# EDCPSUMK2_2040.net
KiCad netlist of a schematic drawn in EAGLE
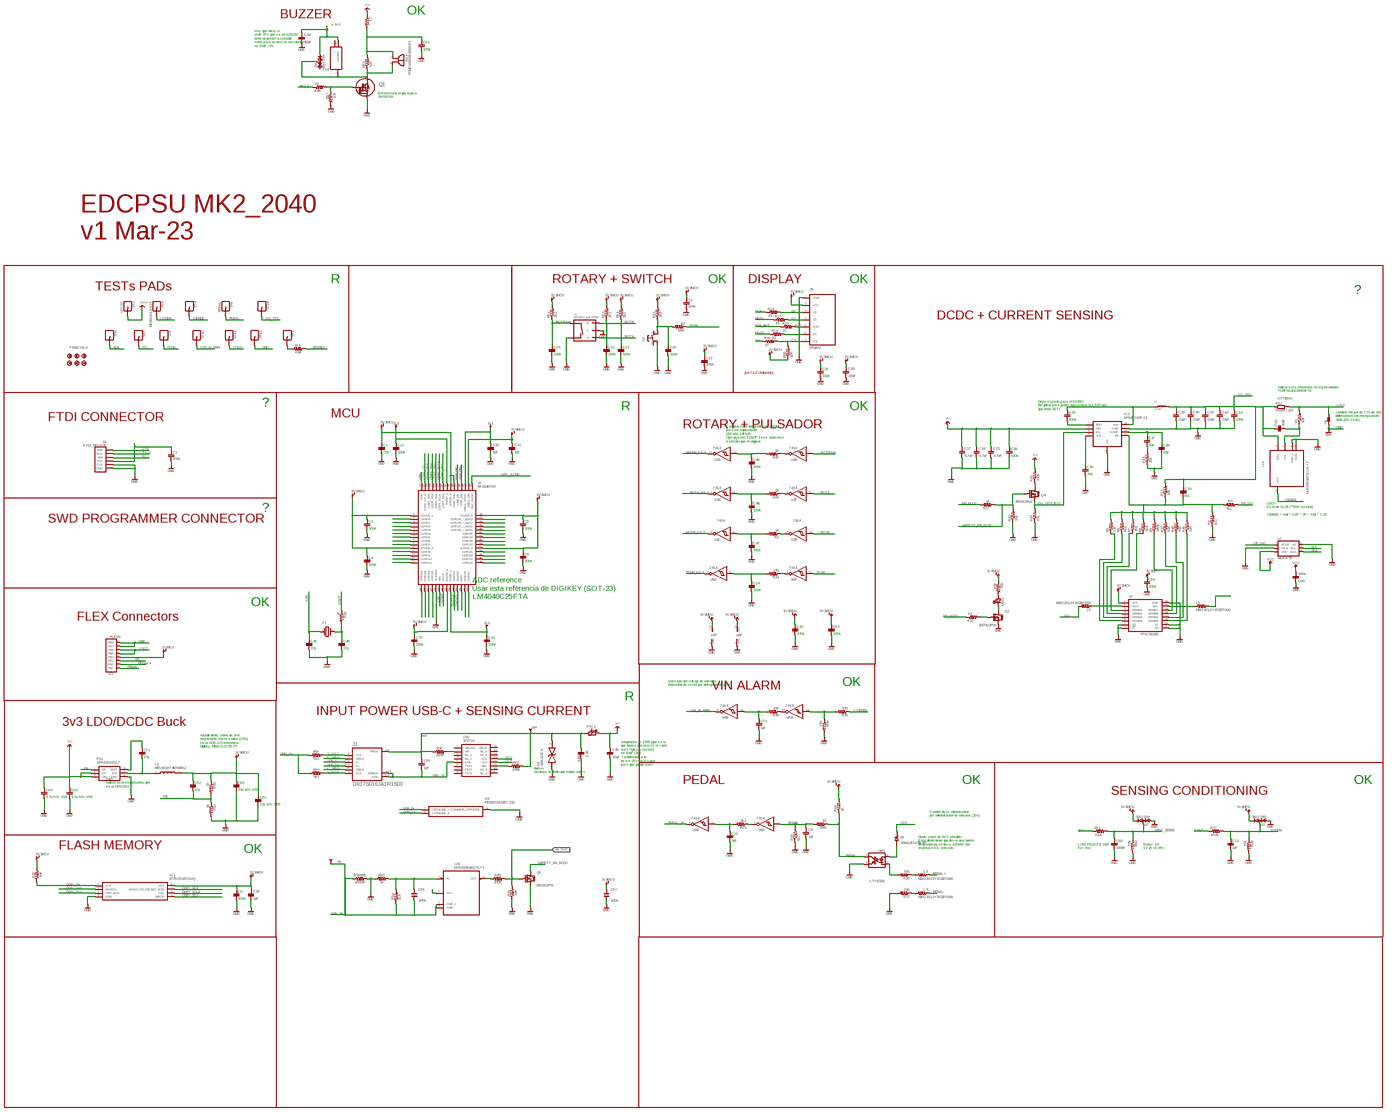
[diagram p0: schematic, sheet 1, overview]
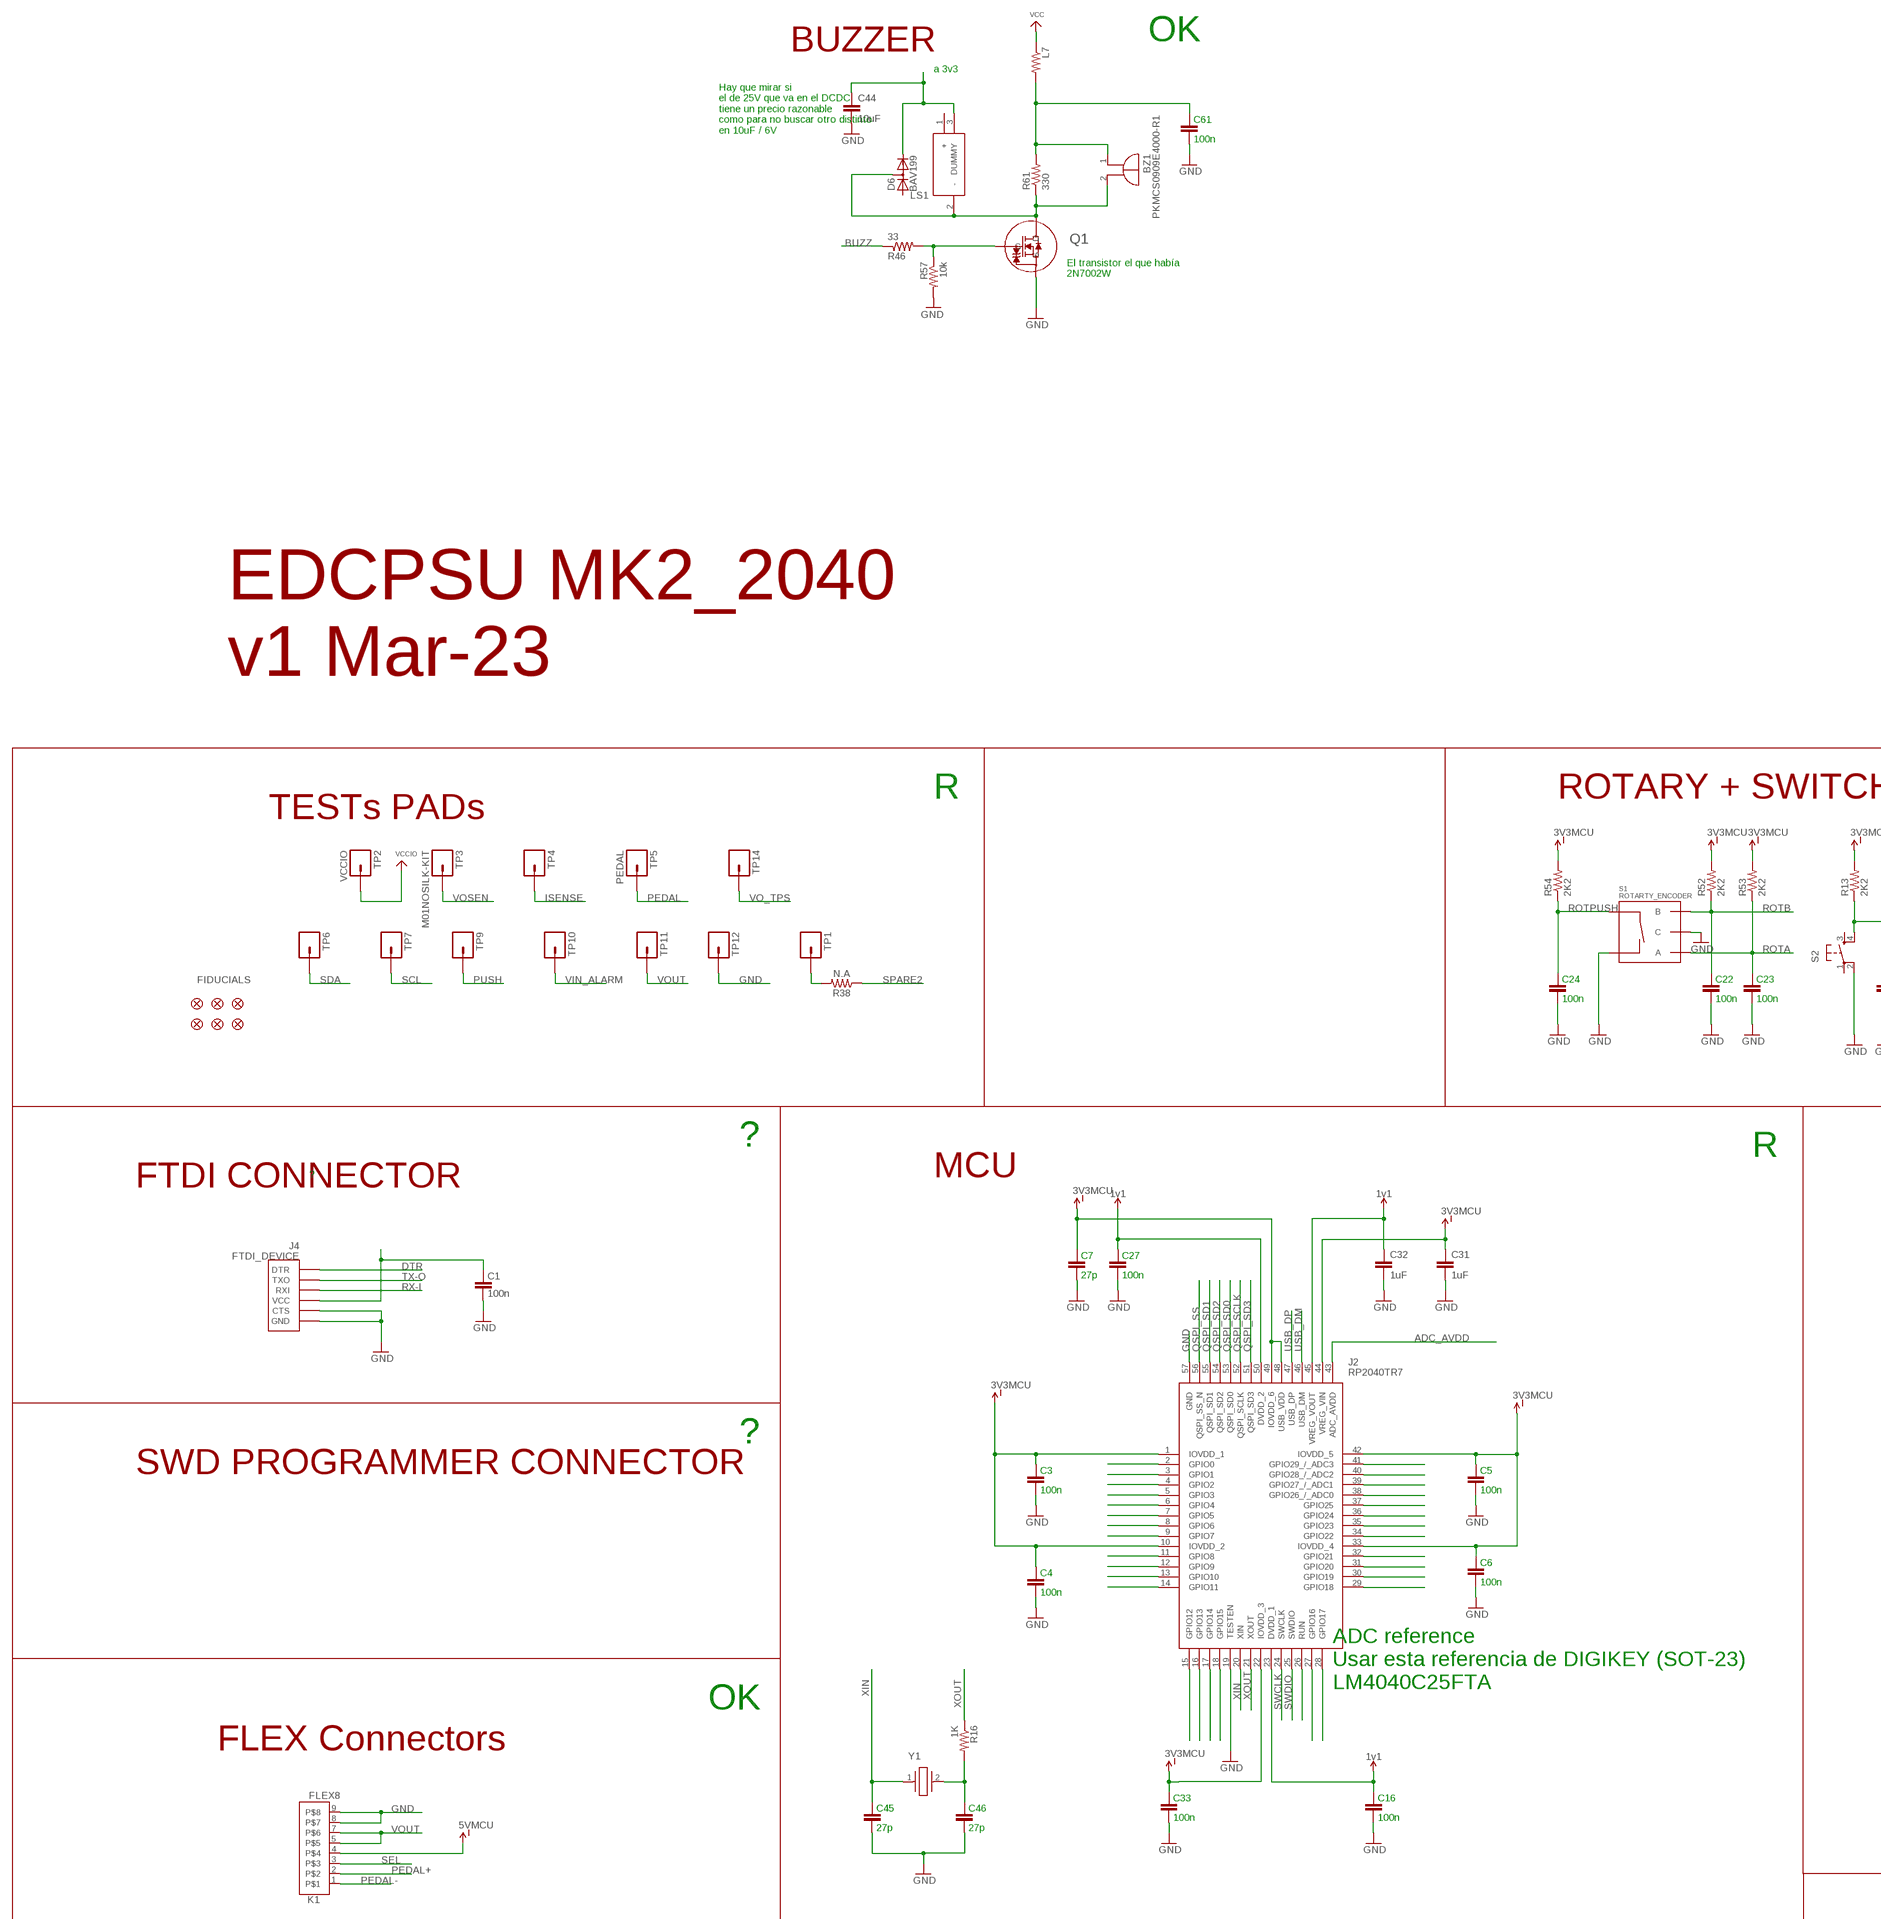
[diagram p1: schematic, sheet 1, part 1 of 4]
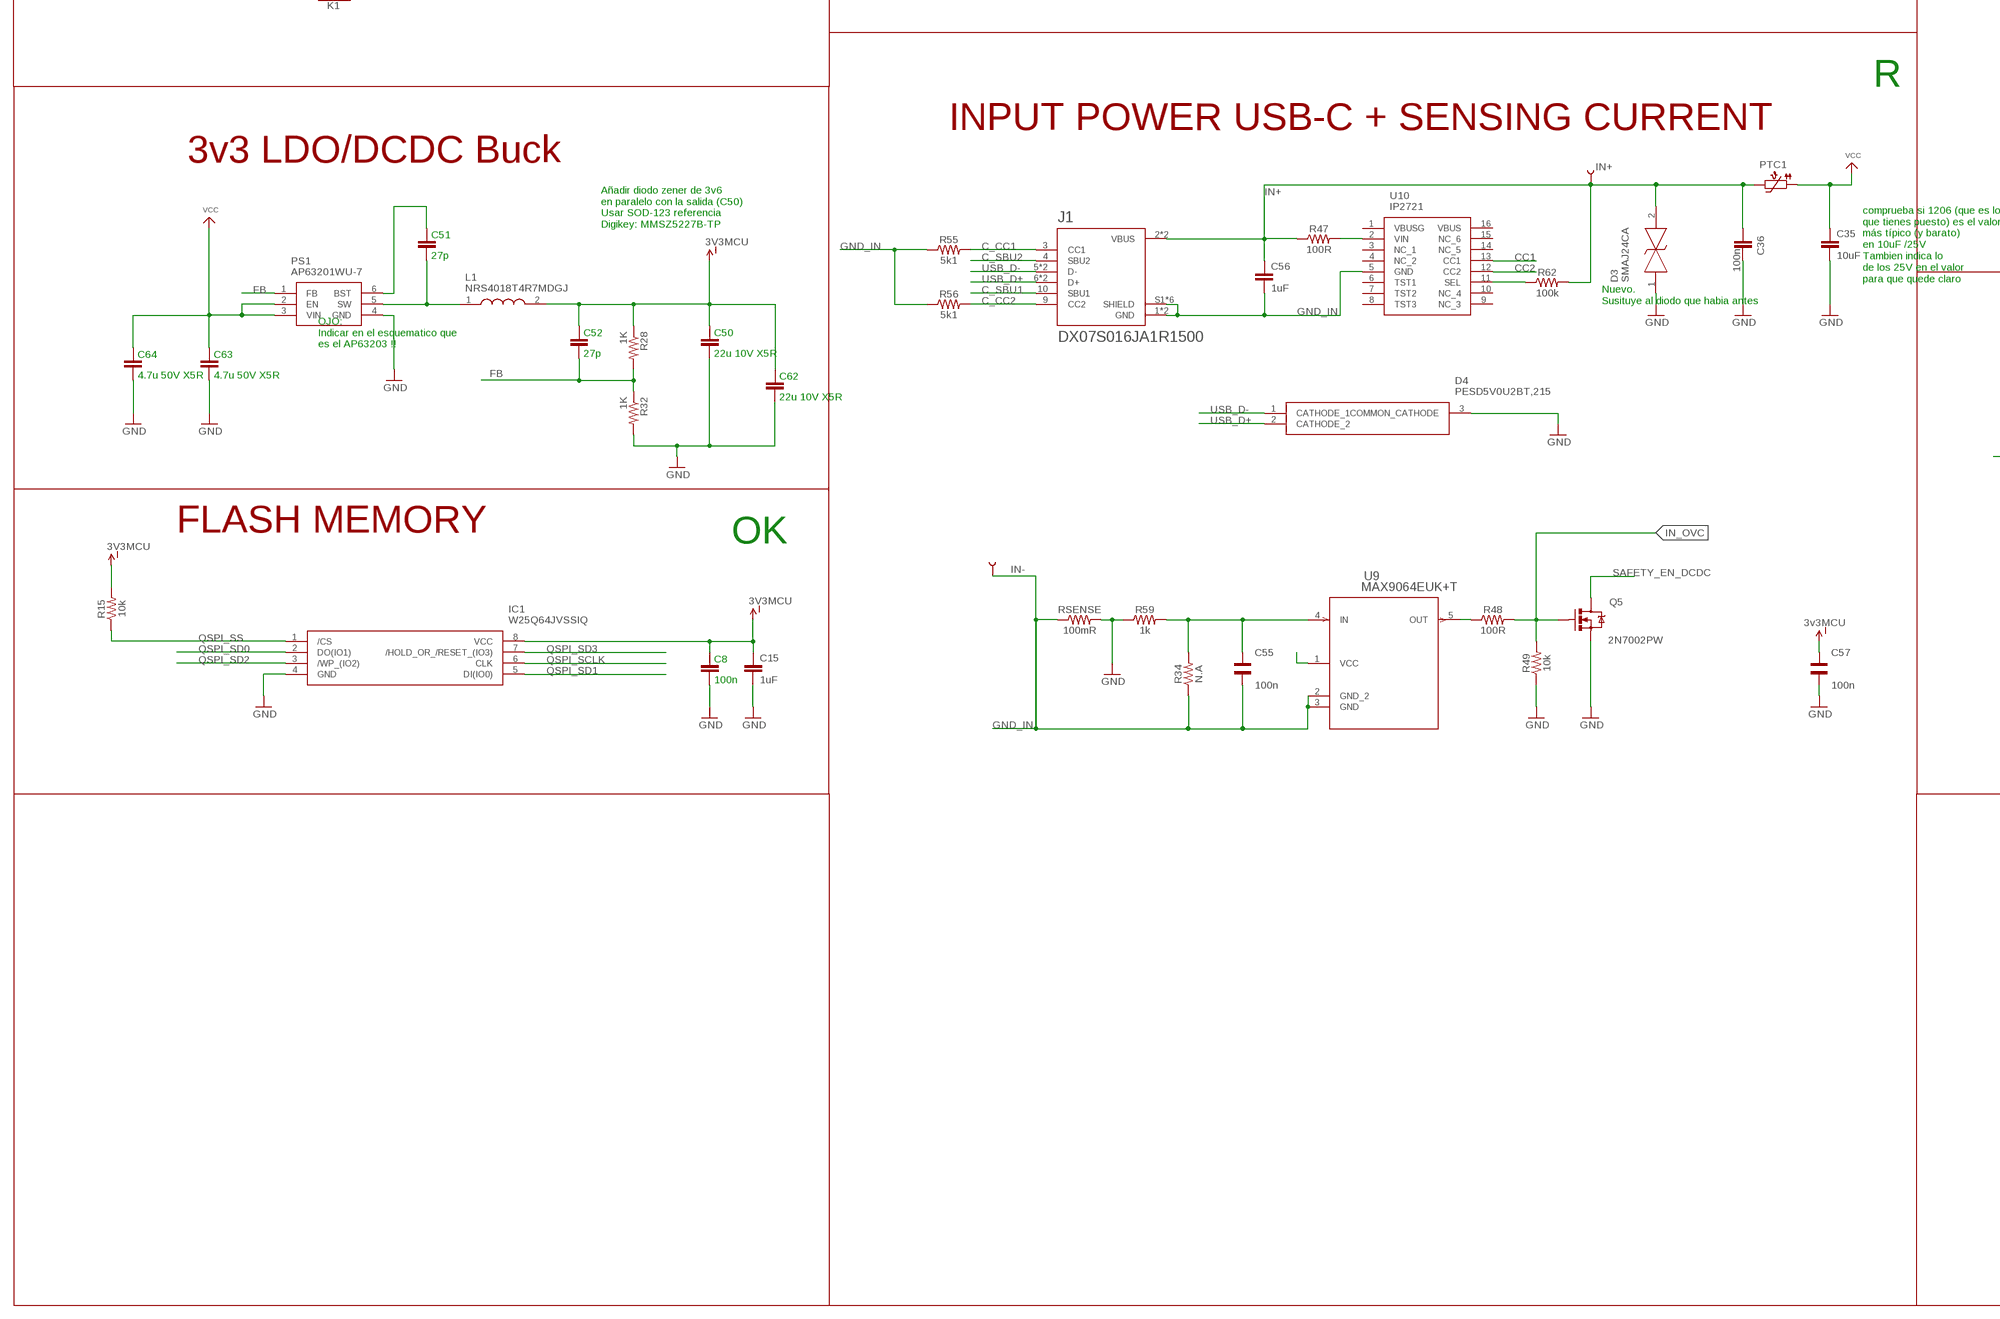
[diagram p2: schematic, sheet 1, part 2 of 4]
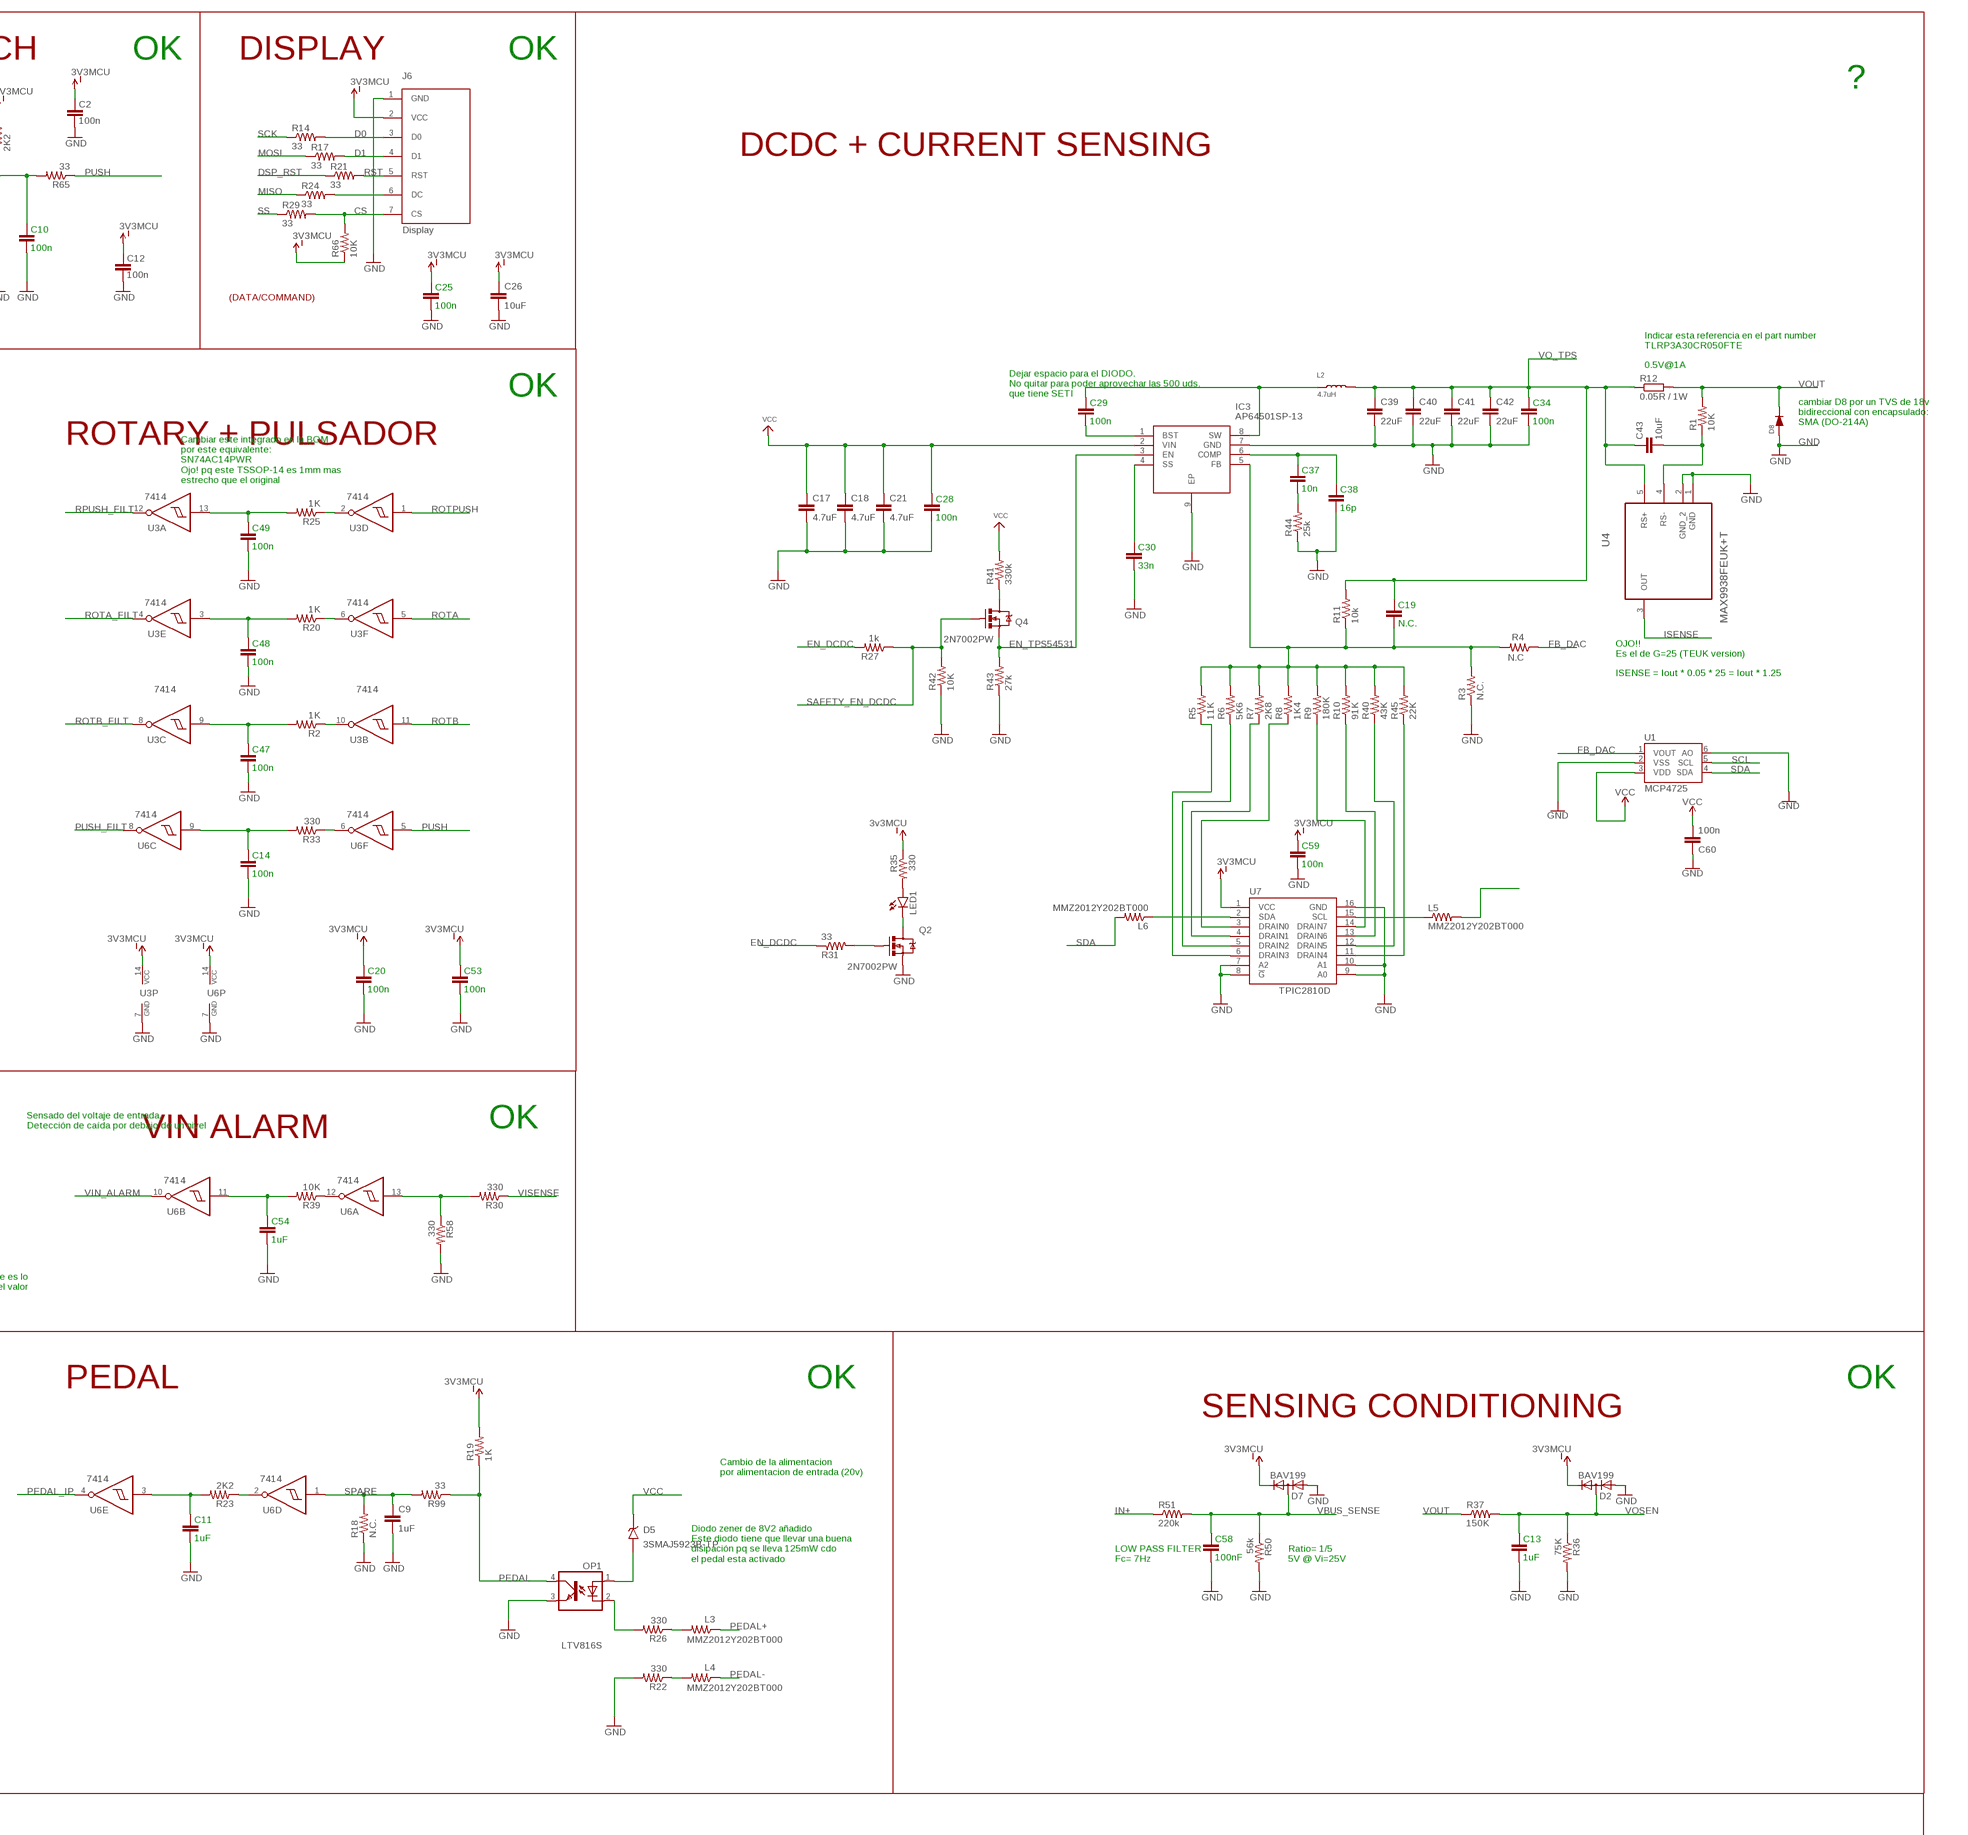
[diagram p3: schematic, sheet 1, part 3 of 4]
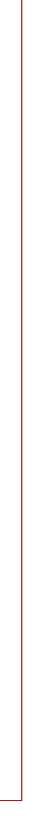
[diagram p4: schematic, sheet 1, part 4 of 4]

(export (version "E")
  (design (tool "Eeschema 10.0.6"))
  (components
    (comp (ref "BZ1")
      (value "PKMCS0909E4000-R1")
      (footprint "eagle-import:PKMCS0909")
      (libsource (lib "eagle-import") (part "PKMCS0909E4000-R1"))
    )
    (comp (ref "C1")
      (value "100n")
      (footprint "eagle-import:0805")
      (libsource (lib "eagle-import") (part "CAP0805"))
    )
    (comp (ref "C2")
      (value "100n")
      (footprint "eagle-import:0805")
      (libsource (lib "eagle-import") (part "CAP0805"))
    )
    (comp (ref "C3")
      (value "100n")
      (footprint "eagle-import:0805")
      (libsource (lib "eagle-import") (part "CAP0805"))
    )
    (comp (ref "C4")
      (value "100n")
      (footprint "eagle-import:0805")
      (libsource (lib "eagle-import") (part "CAP0805"))
    )
    (comp (ref "C5")
      (value "100n")
      (footprint "eagle-import:0805")
      (libsource (lib "eagle-import") (part "CAP0805"))
    )
    (comp (ref "C6")
      (value "100n")
      (footprint "eagle-import:0805")
      (libsource (lib "eagle-import") (part "CAP0805"))
    )
    (comp (ref "C7")
      (value "27p")
      (footprint "eagle-import:0805")
      (libsource (lib "eagle-import") (part "CAP0805"))
    )
    (comp (ref "C8")
      (value "100n")
      (footprint "eagle-import:0805")
      (libsource (lib "eagle-import") (part "CAP0805"))
    )
    (comp (ref "C9")
      (value "1uF")
      (footprint "eagle-import:1206")
      (libsource (lib "eagle-import") (part "SparkFun-Passives_CAP1206"))
    )
    (comp (ref "C10")
      (value "100n")
      (footprint "eagle-import:0805")
      (libsource (lib "eagle-import") (part "CAP0805"))
    )
    (comp (ref "C11")
      (value "1uF")
      (footprint "eagle-import:0805")
      (libsource (lib "eagle-import") (part "CAP0805"))
    )
    (comp (ref "C12")
      (value "100n")
      (footprint "eagle-import:0805")
      (libsource (lib "eagle-import") (part "CAP0805"))
    )
    (comp (ref "C13")
      (value "1uF")
      (footprint "eagle-import:0805")
      (libsource (lib "eagle-import") (part "CAP0805"))
    )
    (comp (ref "C14")
      (value "100n")
      (footprint "eagle-import:0805")
      (libsource (lib "eagle-import") (part "CAP0805"))
    )
    (comp (ref "C15")
      (value "1uF")
      (footprint "eagle-import:1206")
      (libsource (lib "eagle-import") (part "SparkFun-Passives_CAP1206"))
    )
    (comp (ref "C16")
      (value "100n")
      (footprint "eagle-import:0805")
      (libsource (lib "eagle-import") (part "CAP0805"))
    )
    (comp (ref "C17")
      (value "4.7uF")
      (footprint "eagle-import:1210")
      (libsource (lib "eagle-import") (part "SparkFun-Passives_CAP1210"))
    )
    (comp (ref "C18")
      (value "4.7uF")
      (footprint "eagle-import:1210")
      (libsource (lib "eagle-import") (part "SparkFun-Passives_CAP1210"))
    )
    (comp (ref "C19")
      (value "N.C.")
      (footprint "eagle-import:0805")
      (libsource (lib "eagle-import") (part "CAP0805"))
    )
    (comp (ref "C20")
      (value "100n")
      (footprint "eagle-import:0805")
      (libsource (lib "eagle-import") (part "CAP0805"))
    )
    (comp (ref "C21")
      (value "4.7uF")
      (footprint "eagle-import:1210")
      (libsource (lib "eagle-import") (part "SparkFun-Passives_CAP1210"))
    )
    (comp (ref "C22")
      (value "100n")
      (footprint "eagle-import:0805")
      (libsource (lib "eagle-import") (part "CAP0805"))
    )
    (comp (ref "C23")
      (value "100n")
      (footprint "eagle-import:0805")
      (libsource (lib "eagle-import") (part "CAP0805"))
    )
    (comp (ref "C24")
      (value "100n")
      (footprint "eagle-import:0805")
      (libsource (lib "eagle-import") (part "CAP0805"))
    )
    (comp (ref "C25")
      (value "100n")
      (footprint "eagle-import:0805")
      (libsource (lib "eagle-import") (part "CAP0805"))
    )
    (comp (ref "C26")
      (value "10uF")
      (footprint "eagle-import:1206")
      (libsource (lib "eagle-import") (part "SparkFun-Passives_CAP1206"))
    )
    (comp (ref "C27")
      (value "100n")
      (footprint "eagle-import:0805")
      (libsource (lib "eagle-import") (part "CAP0805"))
    )
    (comp (ref "C28")
      (value "100n")
      (footprint "eagle-import:0805")
      (libsource (lib "eagle-import") (part "CAP0805"))
    )
    (comp (ref "C29")
      (value "100n")
      (footprint "eagle-import:0805")
      (libsource (lib "eagle-import") (part "CAP0805"))
    )
    (comp (ref "C30")
      (value "33n")
      (footprint "eagle-import:0805")
      (libsource (lib "eagle-import") (part "CAP0805"))
    )
    (comp (ref "C31")
      (value "1uF")
      (footprint "eagle-import:1206")
      (libsource (lib "eagle-import") (part "SparkFun-Passives_CAP1206"))
    )
    (comp (ref "C32")
      (value "1uF")
      (footprint "eagle-import:1206")
      (libsource (lib "eagle-import") (part "SparkFun-Passives_CAP1206"))
    )
    (comp (ref "C33")
      (value "100n")
      (footprint "eagle-import:0805")
      (libsource (lib "eagle-import") (part "CAP0805"))
    )
    (comp (ref "C34")
      (value "100n")
      (footprint "eagle-import:0805")
      (libsource (lib "eagle-import") (part "CAP0805"))
    )
    (comp (ref "C35")
      (value "10uF")
      (footprint "eagle-import:1206")
      (libsource (lib "eagle-import") (part "SparkFun-Passives_CAP1206"))
    )
    (comp (ref "C36")
      (value "100n")
      (footprint "eagle-import:0805")
      (libsource (lib "eagle-import") (part "CAP0805"))
    )
    (comp (ref "C37")
      (value "10n")
      (footprint "eagle-import:0805")
      (libsource (lib "eagle-import") (part "CAP0805"))
    )
    (comp (ref "C38")
      (value "16p")
      (footprint "eagle-import:0805")
      (libsource (lib "eagle-import") (part "CAP0805"))
    )
    (comp (ref "C39")
      (value "22uF")
      (footprint "eagle-import:1210")
      (libsource (lib "eagle-import") (part "SparkFun-Passives_CAP1210"))
    )
    (comp (ref "C40")
      (value "22uF")
      (footprint "eagle-import:1210")
      (libsource (lib "eagle-import") (part "SparkFun-Passives_CAP1210"))
    )
    (comp (ref "C41")
      (value "22uF")
      (footprint "eagle-import:1210")
      (libsource (lib "eagle-import") (part "SparkFun-Passives_CAP1210"))
    )
    (comp (ref "C42")
      (value "22uF")
      (footprint "eagle-import:1210")
      (libsource (lib "eagle-import") (part "SparkFun-Passives_CAP1210"))
    )
    (comp (ref "C43")
      (value "10uF")
      (footprint "eagle-import:1206")
      (libsource (lib "eagle-import") (part "SparkFun-Passives_CAP1206"))
    )
    (comp (ref "C44")
      (value "10uF")
      (footprint "eagle-import:1206")
      (libsource (lib "eagle-import") (part "SparkFun-Passives_CAP1206"))
    )
    (comp (ref "C45")
      (value "27p")
      (footprint "eagle-import:0805")
      (libsource (lib "eagle-import") (part "CAP0805"))
    )
    (comp (ref "C46")
      (value "27p")
      (footprint "eagle-import:0805")
      (libsource (lib "eagle-import") (part "CAP0805"))
    )
    (comp (ref "C47")
      (value "100n")
      (footprint "eagle-import:0805")
      (libsource (lib "eagle-import") (part "CAP0805"))
    )
    (comp (ref "C48")
      (value "100n")
      (footprint "eagle-import:0805")
      (libsource (lib "eagle-import") (part "CAP0805"))
    )
    (comp (ref "C49")
      (value "100n")
      (footprint "eagle-import:0805")
      (libsource (lib "eagle-import") (part "CAP0805"))
    )
    (comp (ref "C50")
      (value "22u 10V X5R")
      (footprint "eagle-import:0805")
      (libsource (lib "eagle-import") (part "CAP0805"))
    )
    (comp (ref "C51")
      (value "27p")
      (footprint "eagle-import:0805")
      (libsource (lib "eagle-import") (part "CAP0805"))
    )
    (comp (ref "C52")
      (value "27p")
      (footprint "eagle-import:0805")
      (libsource (lib "eagle-import") (part "CAP0805"))
    )
    (comp (ref "C53")
      (value "100n")
      (footprint "eagle-import:0805")
      (libsource (lib "eagle-import") (part "CAP0805"))
    )
    (comp (ref "C54")
      (value "1uF")
      (footprint "eagle-import:0805")
      (libsource (lib "eagle-import") (part "CAP0805"))
    )
    (comp (ref "C55")
      (value "100n")
      (footprint "eagle-import:WCAP-CSGP_1206")
      (libsource (lib "eagle-import") (part "WCAP-CSGP_1206_885012008001"))
    )
    (comp (ref "C56")
      (value "1uF")
      (footprint "eagle-import:1206")
      (libsource (lib "eagle-import") (part "SparkFun-Passives_CAP1206"))
    )
    (comp (ref "C57")
      (value "100n")
      (footprint "eagle-import:WCAP-CSGP_1206")
      (libsource (lib "eagle-import") (part "WCAP-CSGP_1206_885012008001"))
    )
    (comp (ref "C58")
      (value "100nF")
      (footprint "eagle-import:0805")
      (libsource (lib "eagle-import") (part "CAP0805"))
    )
    (comp (ref "C59")
      (value "100n")
      (footprint "eagle-import:0805")
      (libsource (lib "eagle-import") (part "CAP0805"))
    )
    (comp (ref "C60")
      (value "100n")
      (footprint "eagle-import:C0805")
      (libsource (lib "eagle-import") (part "C-EUC0805"))
    )
    (comp (ref "C61")
      (value "100n")
      (footprint "eagle-import:0805")
      (libsource (lib "eagle-import") (part "CAP0805"))
    )
    (comp (ref "C62")
      (value "22u 10V X5R")
      (footprint "eagle-import:0805")
      (libsource (lib "eagle-import") (part "CAP0805"))
    )
    (comp (ref "C63")
      (value "4.7u 50V X5R")
      (footprint "eagle-import:0805")
      (libsource (lib "eagle-import") (part "CAP0805"))
    )
    (comp (ref "C64")
      (value "4.7u 50V X5R")
      (footprint "eagle-import:0805")
      (libsource (lib "eagle-import") (part "CAP0805"))
    )
    (comp (ref "D2")
      (value "BAV199")
      (footprint "eagle-import:SOT23")
      (libsource (lib "eagle-import") (part "BAV199"))
    )
    (comp (ref "D3")
      (value "SMAJ24CA")
      (footprint "eagle-import:DIONM5127X229N")
      (fields (field (name "MOUSER_PART_NUMBER") "652-SMAJ24CA"))
      (libsource (lib "eagle-import") (part "SMAJ24CA"))
    )
    (comp (ref "D4")
      (value "PESD5V0U2BT,215")
      (footprint "eagle-import:SOT95P230X110-3N")
      (fields (field (name "MOUSER_PART_NUMBER") "771-PESD5V0U2BTT/R"))
      (libsource (lib "eagle-import") (part "PESD5V0U2BT,215"))
    )
    (comp (ref "D5")
      (value "3SMAJ5923B-TP")
      (footprint "eagle-import:DIOM4325X244N")
      (fields (field (name "MF") "Micro Commercial Components"))
      (libsource (lib "eagle-import") (part "3SMAJ5923B-TP"))
    )
    (comp (ref "D6")
      (value "BAV199")
      (footprint "eagle-import:SOT23")
      (libsource (lib "eagle-import") (part "BAV199"))
    )
    (comp (ref "D7")
      (value "BAV199")
      (footprint "eagle-import:SOT23")
      (libsource (lib "eagle-import") (part "BAV199"))
    )
    (comp (ref "D8")
      (value "RB060M-60TR")
      (footprint "eagle-import:SMADIODE")
      (libsource (lib "eagle-import") (part "DSMA"))
    )
    (comp (ref "FID1")
      (value "FIDUCIAL1X2")
      (footprint "eagle-import:FIDUCIAL-1X2")
      (libsource (lib "eagle-import") (part "FIDUCIAL1X2"))
    )
    (comp (ref "FID2")
      (value "FIDUCIAL1X2")
      (footprint "eagle-import:FIDUCIAL-1X2")
      (libsource (lib "eagle-import") (part "FIDUCIAL1X2"))
    )
    (comp (ref "FID3")
      (value "FIDUCIAL1X2")
      (footprint "eagle-import:FIDUCIAL-1X2")
      (libsource (lib "eagle-import") (part "FIDUCIAL1X2"))
    )
    (comp (ref "FID4")
      (value "FIDUCIAL1X2")
      (footprint "eagle-import:FIDUCIAL-1X2")
      (libsource (lib "eagle-import") (part "FIDUCIAL1X2"))
    )
    (comp (ref "FID5")
      (value "FIDUCIAL1X2")
      (footprint "eagle-import:FIDUCIAL-1X2")
      (libsource (lib "eagle-import") (part "FIDUCIAL1X2"))
    )
    (comp (ref "FID6")
      (value "FIDUCIAL1X2")
      (footprint "eagle-import:FIDUCIAL-1X2")
      (libsource (lib "eagle-import") (part "FIDUCIAL1X2"))
    )
    (comp (ref "IC1")
      (value "W25Q64JVSSIQ")
      (footprint "eagle-import:SOIC127P790X216-8N")
      (fields (field (name "MOUSER_PART_NUMBER") "454-W25Q64JVSSIQ"))
      (libsource (lib "eagle-import") (part "W25Q64JVSSIQ"))
    )
    (comp (ref "IC3")
      (value "AP64501SP-13")
      (footprint "eagle-import:SOIC127P600X163-9N")
      (fields (field (name "MOUSER_PART_NUMBER") "621-AP64501SP-13"))
      (libsource (lib "eagle-import") (part "AP64501SP-13"))
    )
    (comp (ref "IN+")
      (value "TEST-POINT3")
      (footprint "eagle-import:PAD.03X.03")
      (libsource (lib "eagle-import") (part "TEST-POINT3"))
    )
    (comp (ref "IN-")
      (value "TEST-POINT3")
      (footprint "eagle-import:PAD.03X.03")
      (libsource (lib "eagle-import") (part "TEST-POINT3"))
    )
    (comp (ref "J1")
      (value "DX07S016JA1R1500")
      (footprint "eagle-import:JAE_DX07S016JA1R1500")
      (fields
        (field (name "DIGI-KEY_PART_NUMBER") "670-DX07S016JA1R1500CT-ND")
        (field (name "MF") "JAE Electronics")
      )
      (libsource (lib "eagle-import") (part "DX07S016JA1R1500"))
    )
    (comp (ref "J2")
      (value "RP2040TR7")
      (footprint "eagle-import:RP2040TR7")
      (libsource (lib "eagle-import") (part "RP2040TR7"))
    )
    (comp (ref "J4")
      (value "FTDI_DEVICE")
      (footprint "eagle-import:FTDI_DEVICE_SIDE")
      (libsource (lib "eagle-import") (part "FTDI_DEVICE"))
    )
    (comp (ref "J6")
      (value "Display")
      (footprint "eagle-import:OLED_LCD")
      (libsource (lib "eagle-import") (part "OLED_LCD"))
    )
    (comp (ref "K1")
      (value "FLEX8")
      (footprint "eagle-import:FLEX8")
      (libsource (lib "eagle-import") (part "FLEX8"))
    )
    (comp (ref "L1")
      (value "NRS4018T4R7MDGJ")
      (footprint "eagle-import:NRS4018T100MDGJ")
      (fields (field (name "MOUSER_PART_NUMBER") "963-NRS4018T4R7MDGJ"))
      (libsource (lib "eagle-import") (part "NRS4018T4R7MDGJ"))
    )
    (comp (ref "L2")
      (value "4.7uH")
      (footprint "eagle-import:WE-LHMI")
      (libsource (lib "eagle-import") (part "L74437368047"))
    )
    (comp (ref "L3")
      (value "MMZ2012Y202BT000")
      (footprint "eagle-import:0805")
      (libsource (lib "eagle-import") (part "RESISTOR0805-RES"))
    )
    (comp (ref "L4")
      (value "MMZ2012Y202BT000")
      (footprint "eagle-import:0805")
      (libsource (lib "eagle-import") (part "RESISTOR0805-RES"))
    )
    (comp (ref "L5")
      (value "MMZ2012Y202BT000")
      (footprint "eagle-import:0805")
      (libsource (lib "eagle-import") (part "RESISTOR0805-RES"))
    )
    (comp (ref "L6")
      (value "MMZ2012Y202BT000")
      (footprint "eagle-import:0805")
      (libsource (lib "eagle-import") (part "RESISTOR0805-RES"))
    )
    (comp (ref "L7")
      (value "MMZ2012Y202BT000")
      (footprint "eagle-import:0805")
      (libsource (lib "eagle-import") (part "RESISTOR0805-RES"))
    )
    (comp (ref "LED1")
      (value "LED3MM")
      (footprint "eagle-import:LED3MM")
      (libsource (lib "eagle-import") (part "LED3MM"))
    )
    (comp (ref "LS1")
      (value "SMT-0540-S-R")
      (footprint "eagle-import:SMT0540SR")
      (fields (field (name "MOUSER_PART_NUMBER") "665-SMT0540SR"))
      (libsource (lib "eagle-import") (part "SMT-0540-S-R"))
    )
    (comp (ref "OP1")
      (value "LTV816S")
      (footprint "eagle-import:SMD4")
      (libsource (lib "eagle-import") (part "LTV816S"))
    )
    (comp (ref "PS1")
      (value "AP63201WU-7")
      (footprint "eagle-import:SOT95P280X100-6N")
      (fields (field (name "MOUSER_PART_NUMBER") "621-AP63201WU-7"))
      (libsource (lib "eagle-import") (part "AP63201WU-7"))
    )
    (comp (ref "PTC1")
      (value "2A NOM / 3.5A LIM")
      (footprint "eagle-import:1812L")
      (libsource (lib "eagle-import") (part "PTC-"))
    )
    (comp (ref "Q1")
      (value "PJA3416AE_R1_00001")
      (footprint "eagle-import:SOT23_PJA3416_PNJ")
      (fields (field (name "COPYRIGHT") "Copyright (C) 2022 Ultra Librarian. All rights reserved."))
      (libsource (lib "eagle-import") (part "PJA3416AE_R1_00001"))
    )
    (comp (ref "Q2")
      (value "2N7002PW")
      (footprint "eagle-import:SOT323")
      (libsource (lib "eagle-import") (part "MOSFET-NCHANNEL2N7002PW"))
    )
    (comp (ref "Q4")
      (value "2N7002PW")
      (footprint "eagle-import:SOT323")
      (libsource (lib "eagle-import") (part "MOSFET-NCHANNEL2N7002PW"))
    )
    (comp (ref "Q5")
      (value "2N7002PW")
      (footprint "eagle-import:SOT323")
      (libsource (lib "eagle-import") (part "MOSFET-NCHANNEL2N7002PW"))
    )
    (comp (ref "R1")
      (value "10K")
      (footprint "eagle-import:0805")
      (libsource (lib "eagle-import") (part "RESISTOR0805-RES"))
    )
    (comp (ref "R2")
      (value "1K")
      (footprint "eagle-import:0805")
      (libsource (lib "eagle-import") (part "RESISTOR0805-RES"))
    )
    (comp (ref "R3")
      (value "N.C.")
      (footprint "eagle-import:0805")
      (libsource (lib "eagle-import") (part "RESISTOR0805-RES"))
    )
    (comp (ref "R4")
      (value "N.C")
      (footprint "eagle-import:0805")
      (libsource (lib "eagle-import") (part "RESISTOR0805-RES"))
    )
    (comp (ref "R5")
      (value "11K")
      (footprint "eagle-import:0805")
      (libsource (lib "eagle-import") (part "RESISTOR0805-RES"))
    )
    (comp (ref "R6")
      (value "5K6")
      (footprint "eagle-import:0805")
      (libsource (lib "eagle-import") (part "RESISTOR0805-RES"))
    )
    (comp (ref "R7")
      (value "2K8")
      (footprint "eagle-import:0805")
      (libsource (lib "eagle-import") (part "RESISTOR0805-RES"))
    )
    (comp (ref "R8")
      (value "1K4")
      (footprint "eagle-import:0805")
      (libsource (lib "eagle-import") (part "RESISTOR0805-RES"))
    )
    (comp (ref "R9")
      (value "180K")
      (footprint "eagle-import:0805")
      (libsource (lib "eagle-import") (part "RESISTOR0805-RES"))
    )
    (comp (ref "R10")
      (value "91K")
      (footprint "eagle-import:0805")
      (libsource (lib "eagle-import") (part "RESISTOR0805-RES"))
    )
    (comp (ref "R11")
      (value "10k")
      (footprint "eagle-import:0805")
      (libsource (lib "eagle-import") (part "RESISTOR0805-RES"))
    )
    (comp (ref "R12")
      (value "0.05R / 1W")
      (footprint "eagle-import:R2512")
      (libsource (lib "eagle-import") (part "RR2512"))
    )
    (comp (ref "R13")
      (value "2K2")
      (footprint "eagle-import:0805")
      (libsource (lib "eagle-import") (part "RESISTOR0805-RES"))
    )
    (comp (ref "R14")
      (value "33")
      (footprint "eagle-import:0805")
      (libsource (lib "eagle-import") (part "RESISTOR0805-RES"))
    )
    (comp (ref "R15")
      (value "10k")
      (footprint "eagle-import:0603")
      (libsource (lib "eagle-import") (part "RESISTOR0603"))
    )
    (comp (ref "R16")
      (value "1K")
      (footprint "eagle-import:0805")
      (libsource (lib "eagle-import") (part "RESISTOR0805-RES"))
    )
    (comp (ref "R17")
      (value "33")
      (footprint "eagle-import:0805")
      (libsource (lib "eagle-import") (part "RESISTOR0805-RES"))
    )
    (comp (ref "R18")
      (value "N.C.")
      (footprint "eagle-import:0805")
      (libsource (lib "eagle-import") (part "RESISTOR0805-RES"))
    )
    (comp (ref "R19")
      (value "1K")
      (footprint "eagle-import:0805")
      (libsource (lib "eagle-import") (part "RESISTOR0805-RES"))
    )
    (comp (ref "R20")
      (value "1K")
      (footprint "eagle-import:0805")
      (libsource (lib "eagle-import") (part "RESISTOR0805-RES"))
    )
    (comp (ref "R21")
      (value "33")
      (footprint "eagle-import:0805")
      (libsource (lib "eagle-import") (part "RESISTOR0805-RES"))
    )
    (comp (ref "R22")
      (value "330")
      (footprint "eagle-import:1206")
      (libsource (lib "eagle-import") (part "SparkFun-Passives_RESISTOR1206"))
    )
    (comp (ref "R23")
      (value "2K2")
      (footprint "eagle-import:0805")
      (libsource (lib "eagle-import") (part "RESISTOR0805-RES"))
    )
    (comp (ref "R24")
      (value "33")
      (footprint "eagle-import:0805")
      (libsource (lib "eagle-import") (part "RESISTOR0805-RES"))
    )
    (comp (ref "R25")
      (value "1K")
      (footprint "eagle-import:0805")
      (libsource (lib "eagle-import") (part "RESISTOR0805-RES"))
    )
    (comp (ref "R26")
      (value "330")
      (footprint "eagle-import:1206")
      (libsource (lib "eagle-import") (part "SparkFun-Passives_RESISTOR1206"))
    )
    (comp (ref "R27")
      (value "1k")
      (footprint "eagle-import:0805")
      (libsource (lib "eagle-import") (part "RESISTOR0805-RES"))
    )
    (comp (ref "R28")
      (value "1K")
      (footprint "eagle-import:0805")
      (libsource (lib "eagle-import") (part "RESISTOR0805-RES"))
    )
    (comp (ref "R29")
      (value "33")
      (footprint "eagle-import:0805")
      (libsource (lib "eagle-import") (part "RESISTOR0805-RES"))
    )
    (comp (ref "R30")
      (value "330")
      (footprint "eagle-import:0805")
      (libsource (lib "eagle-import") (part "RESISTOR0805-RES"))
    )
    (comp (ref "R31")
      (value "33")
      (footprint "eagle-import:0805")
      (libsource (lib "eagle-import") (part "RESISTOR0805-RES"))
    )
    (comp (ref "R32")
      (value "1K")
      (footprint "eagle-import:0805")
      (libsource (lib "eagle-import") (part "RESISTOR0805-RES"))
    )
    (comp (ref "R33")
      (value "330")
      (footprint "eagle-import:0805")
      (libsource (lib "eagle-import") (part "RESISTOR0805-RES"))
    )
    (comp (ref "R34")
      (value "N.A")
      (footprint "eagle-import:0603")
      (libsource (lib "eagle-import") (part "RESISTOR0603"))
    )
    (comp (ref "R35")
      (value "330")
      (footprint "eagle-import:0805")
      (libsource (lib "eagle-import") (part "RESISTOR0805-RES"))
    )
    (comp (ref "R36")
      (value "75K")
      (footprint "eagle-import:0805")
      (libsource (lib "eagle-import") (part "RESISTOR0805-RES"))
    )
    (comp (ref "R37")
      (value "150K")
      (footprint "eagle-import:0805")
      (libsource (lib "eagle-import") (part "RESISTOR0805-RES"))
    )
    (comp (ref "R38")
      (value "N.A")
      (footprint "eagle-import:0603")
      (libsource (lib "eagle-import") (part "RESISTOR0603"))
    )
    (comp (ref "R39")
      (value "10K")
      (footprint "eagle-import:0805")
      (libsource (lib "eagle-import") (part "RESISTOR0805-RES"))
    )
    (comp (ref "R40")
      (value "43K")
      (footprint "eagle-import:0805")
      (libsource (lib "eagle-import") (part "RESISTOR0805-RES"))
    )
    (comp (ref "R41")
      (value "330k")
      (footprint "eagle-import:0805")
      (libsource (lib "eagle-import") (part "RESISTOR0805-RES"))
    )
    (comp (ref "R42")
      (value "10K")
      (footprint "eagle-import:0805")
      (libsource (lib "eagle-import") (part "RESISTOR0805-RES"))
    )
    (comp (ref "R43")
      (value "27k")
      (footprint "eagle-import:0805")
      (libsource (lib "eagle-import") (part "RESISTOR0805-RES"))
    )
    (comp (ref "R44")
      (value "25k")
      (footprint "eagle-import:0805")
      (libsource (lib "eagle-import") (part "RESISTOR0805-RES"))
    )
    (comp (ref "R45")
      (value "22K")
      (footprint "eagle-import:0805")
      (libsource (lib "eagle-import") (part "RESISTOR0805-RES"))
    )
    (comp (ref "R46")
      (value "33")
      (footprint "eagle-import:0805")
      (libsource (lib "eagle-import") (part "RESISTOR0805-RES"))
    )
    (comp (ref "R47")
      (value "100R")
      (footprint "eagle-import:0603")
      (libsource (lib "eagle-import") (part "RESISTOR0603"))
    )
    (comp (ref "R48")
      (value "100R")
      (footprint "eagle-import:0603")
      (libsource (lib "eagle-import") (part "RESISTOR0603"))
    )
    (comp (ref "R49")
      (value "10k")
      (footprint "eagle-import:0603")
      (libsource (lib "eagle-import") (part "RESISTOR0603"))
    )
    (comp (ref "R50")
      (value "56k")
      (footprint "eagle-import:0603")
      (libsource (lib "eagle-import") (part "RESISTOR0603"))
    )
    (comp (ref "R51")
      (value "220k")
      (footprint "eagle-import:0603")
      (libsource (lib "eagle-import") (part "RESISTOR0603"))
    )
    (comp (ref "R52")
      (value "2K2")
      (footprint "eagle-import:0805")
      (libsource (lib "eagle-import") (part "RESISTOR0805-RES"))
    )
    (comp (ref "R53")
      (value "2K2")
      (footprint "eagle-import:0805")
      (libsource (lib "eagle-import") (part "RESISTOR0805-RES"))
    )
    (comp (ref "R54")
      (value "2K2")
      (footprint "eagle-import:0805")
      (libsource (lib "eagle-import") (part "RESISTOR0805-RES"))
    )
    (comp (ref "R55")
      (value "5k1")
      (footprint "eagle-import:0603")
      (libsource (lib "eagle-import") (part "RESISTOR0603"))
    )
    (comp (ref "R56")
      (value "5k1")
      (footprint "eagle-import:0603")
      (libsource (lib "eagle-import") (part "RESISTOR0603"))
    )
    (comp (ref "R57")
      (value "10k")
      (footprint "eagle-import:0805")
      (libsource (lib "eagle-import") (part "RESISTOR0805-RES"))
    )
    (comp (ref "R58")
      (value "330")
      (footprint "eagle-import:0805")
      (libsource (lib "eagle-import") (part "RESISTOR0805-RES"))
    )
    (comp (ref "R59")
      (value "1k")
      (footprint "eagle-import:0603")
      (libsource (lib "eagle-import") (part "RESISTOR0603"))
    )
    (comp (ref "R61")
      (value "330")
      (footprint "eagle-import:0805")
      (libsource (lib "eagle-import") (part "RESISTOR0805-RES"))
    )
    (comp (ref "R62")
      (value "100k")
      (footprint "eagle-import:0603")
      (libsource (lib "eagle-import") (part "RESISTOR0603"))
    )
    (comp (ref "R65")
      (value "33")
      (footprint "eagle-import:0805")
      (libsource (lib "eagle-import") (part "RESISTOR0805-RES"))
    )
    (comp (ref "R66")
      (value "10K")
      (footprint "eagle-import:0805")
      (libsource (lib "eagle-import") (part "RESISTOR0805-RES"))
    )
    (comp (ref "R99")
      (value "33")
      (footprint "eagle-import:0805")
      (libsource (lib "eagle-import") (part "RESISTOR0805-RES"))
    )
    (comp (ref "RSENSE")
      (value "100mR")
      (footprint "eagle-import:1206")
      (libsource (lib "eagle-import") (part "SparkFun-Resistors_532_RESISTOR1206"))
    )
    (comp (ref "S1")
      (value "ROTARTY_ENCODER")
      (footprint "eagle-import:ROTARY_ENC_PLAIN")
      (libsource (lib "eagle-import") (part "ROTARTY_ENCODER"))
    )
    (comp (ref "S2")
      (value "TAC_SWITCH_KSC931G-SMD")
      (footprint "eagle-import:TAC_SW_SMD_KSC931G")
      (libsource (lib "eagle-import") (part "TAC_SWITCH_KSC931G-SMD"))
    )
    (comp (ref "TP1")
      (value "M01POGOPIN_HOLE_LARGE")
      (footprint "eagle-import:1X01_POGOPIN_HOLE_LARGE")
      (libsource (lib "eagle-import") (part "M01POGOPIN_HOLE_LARGE"))
    )
    (comp (ref "TP2")
      (value "VCCIO")
      (footprint "eagle-import:1X01_POGOPIN_HOLE_LARGE")
      (libsource (lib "eagle-import") (part "M01POGOPIN_HOLE_LARGE"))
    )
    (comp (ref "TP3")
      (value "M01NOSILK-KIT")
      (footprint "eagle-import:1X01NS-KIT")
      (libsource (lib "eagle-import") (part "M01NOSILK-KIT"))
    )
    (comp (ref "TP4")
      (value "M01POGOPIN_HOLE_LARGE")
      (footprint "eagle-import:1X01_POGOPIN_HOLE_LARGE")
      (libsource (lib "eagle-import") (part "M01POGOPIN_HOLE_LARGE"))
    )
    (comp (ref "TP5")
      (value "PEDAL")
      (footprint "eagle-import:1X01_POGOPIN_HOLE_LARGE")
      (libsource (lib "eagle-import") (part "M01POGOPIN_HOLE_LARGE"))
    )
    (comp (ref "TP6")
      (value "M01POGOPIN_HOLE_LARGE")
      (footprint "eagle-import:1X01_POGOPIN_HOLE_LARGE")
      (libsource (lib "eagle-import") (part "M01POGOPIN_HOLE_LARGE"))
    )
    (comp (ref "TP7")
      (value "M01POGOPIN_HOLE_LARGE")
      (footprint "eagle-import:1X01_POGOPIN_HOLE_LARGE")
      (libsource (lib "eagle-import") (part "M01POGOPIN_HOLE_LARGE"))
    )
    (comp (ref "TP9")
      (value "M01POGOPIN_HOLE_LARGE")
      (footprint "eagle-import:1X01_POGOPIN_HOLE_LARGE")
      (libsource (lib "eagle-import") (part "M01POGOPIN_HOLE_LARGE"))
    )
    (comp (ref "TP10")
      (value "M01POGOPIN_HOLE_LARGE")
      (footprint "eagle-import:1X01_POGOPIN_HOLE_LARGE")
      (libsource (lib "eagle-import") (part "M01POGOPIN_HOLE_LARGE"))
    )
    (comp (ref "TP11")
      (value "M01POGOPIN_HOLE_LARGE")
      (footprint "eagle-import:1X01_POGOPIN_HOLE_LARGE")
      (libsource (lib "eagle-import") (part "M01POGOPIN_HOLE_LARGE"))
    )
    (comp (ref "TP12")
      (value "M01POGOPIN_HOLE_LARGE")
      (footprint "eagle-import:1X01_POGOPIN_HOLE_LARGE")
      (libsource (lib "eagle-import") (part "M01POGOPIN_HOLE_LARGE"))
    )
    (comp (ref "TP14")
      (value "M01POGOPIN_HOLE_LARGE")
      (footprint "eagle-import:1X01_POGOPIN_HOLE_LARGE")
      (libsource (lib "eagle-import") (part "M01POGOPIN_HOLE_LARGE"))
    )
    (comp (ref "U1")
      (value "MCP4725")
      (footprint "eagle-import:SOT23-6")
      (libsource (lib "eagle-import") (part "MCP4725SOT-23"))
    )
    (comp (ref "U3")
      (value "7414")
      (footprint "eagle-import:TSSOP14")
      (libsource (lib "eagle-import") (part "7414"))
    )
    (comp (ref "U4")
      (value "MAX9938FEUK+T")
      (footprint "eagle-import:SOT95P280X145-5N")
      (libsource (lib "eagle-import") (part "MAX9938FEUK+T"))
    )
    (comp (ref "U6")
      (value "7414")
      (footprint "eagle-import:TSSOP14")
      (libsource (lib "eagle-import") (part "7414"))
    )
    (comp (ref "U7")
      (value "TPIC2810D")
      (footprint "eagle-import:SO16")
      (libsource (lib "eagle-import") (part "TPIC2810D"))
    )
    (comp (ref "U9")
      (value "MAX9064EUK+T")
      (footprint "eagle-import:21-0057F_MXM")
      (fields (field (name "COPYRIGHT") "Copyright (C) 2022 Ultra Librarian. All rights reserved."))
      (libsource (lib "eagle-import") (part "MAX9064EUK+T"))
    )
    (comp (ref "U10")
      (value "IP2721")
      (footprint "eagle-import:SOP65P640X120-16N")
      (libsource (lib "eagle-import") (part "IP2721"))
    )
    (comp (ref "Y1")
      (value "ABLS-12.000MHZ-B4-T")
      (footprint "eagle-import:ABLS")
      (fields (field (name "MOUSER_PART_NUMBER") "815-ABLS-12.0M-T"))
      (libsource (lib "eagle-import") (part "ABLS-12.000MHZ-B4-T"))
    )
  )
  (nets
    (net (code "1") (name "/ADC_AVDD") (class "Default")
      (node (ref "J2") (pin "43") (pinfunction "ADC_AVDD_43") (pintype "bidirectional"))
    )
    (net (code "2") (name "/BUZZ") (class "Default")
      (node (ref "R46") (pin "1") (pinfunction "1_1") (pintype "passive"))
    )
    (net (code "3") (name "/CC1") (class "Default")
      (node (ref "U10") (pin "13") (pinfunction "CC1_13") (pintype "bidirectional"))
    )
    (net (code "4") (name "/CC2") (class "Default")
      (node (ref "U10") (pin "12") (pinfunction "CC2_12") (pintype "bidirectional"))
    )
    (net (code "5") (name "/CS") (class "Default")
      (node (ref "J6") (pin "7") (pinfunction "CS_7") (pintype "bidirectional"))
      (node (ref "R29") (pin "2") (pinfunction "2_2") (pintype "passive"))
      (node (ref "R66") (pin "2") (pinfunction "2_2") (pintype "passive"))
    )
    (net (code "6") (name "/C_CC1") (class "Default")
      (node (ref "J1") (pin "3") (pinfunction "CC1_3") (pintype "passive"))
      (node (ref "R55") (pin "2") (pinfunction "2_2") (pintype "passive"))
    )
    (net (code "7") (name "/C_CC2") (class "Default")
      (node (ref "J1") (pin "9") (pinfunction "CC2_9") (pintype "passive"))
      (node (ref "R56") (pin "2") (pinfunction "2_2") (pintype "passive"))
    )
    (net (code "8") (name "/C_SBU1") (class "Default")
      (node (ref "J1") (pin "10") (pinfunction "SBU1_10") (pintype "passive"))
    )
    (net (code "9") (name "/C_SBU2") (class "Default")
      (node (ref "J1") (pin "4") (pinfunction "SBU2_4") (pintype "passive"))
    )
    (net (code "10") (name "/D0") (class "Default")
      (node (ref "J6") (pin "3") (pinfunction "D0_3") (pintype "bidirectional"))
      (node (ref "R14") (pin "2") (pinfunction "2_2") (pintype "passive"))
    )
    (net (code "11") (name "/D1") (class "Default")
      (node (ref "J6") (pin "4") (pinfunction "D1_4") (pintype "bidirectional"))
      (node (ref "R17") (pin "2") (pinfunction "2_2") (pintype "passive"))
    )
    (net (code "12") (name "/DSP_RST") (class "Default")
      (node (ref "R21") (pin "1") (pinfunction "1_1") (pintype "passive"))
    )
    (net (code "13") (name "/DTR") (class "Default")
      (node (ref "J4") (pin "P$1") (pinfunction "DTR_P$1") (pintype "bidirectional"))
    )
    (net (code "14") (name "/EN_DCDC") (class "Default")
      (node (ref "R27") (pin "2") (pinfunction "2_2") (pintype "passive"))
      (node (ref "R31") (pin "1") (pinfunction "1_1") (pintype "passive"))
    )
    (net (code "15") (name "/EN_TPS54531") (class "Default")
      (node (ref "IC3") (pin "3") (pinfunction "EN_3") (pintype "bidirectional"))
      (node (ref "Q4") (pin "2") (pinfunction "S_2") (pintype "passive"))
      (node (ref "R43") (pin "2") (pinfunction "2_2") (pintype "passive"))
    )
    (net (code "16") (name "/FB") (class "Default")
      (node (ref "C52") (pin "1") (pinfunction "1_1") (pintype "passive"))
      (node (ref "PS1") (pin "1") (pinfunction "FB_1") (pintype "bidirectional"))
      (node (ref "R28") (pin "2") (pinfunction "2_2") (pintype "passive"))
      (node (ref "R32") (pin "1") (pinfunction "1_1") (pintype "passive"))
    )
    (net (code "17") (name "/FB_DAC") (class "Default")
      (node (ref "R4") (pin "1") (pinfunction "1_1") (pintype "passive"))
      (node (ref "U1") (pin "1") (pinfunction "VOUT_1") (pintype "bidirectional"))
    )
    (net (code "18") (name "/GND_IN") (class "Default")
      (node (ref "C55") (pin "1") (pinfunction "1_1") (pintype "passive"))
      (node (ref "C56") (pin "2") (pinfunction "2_2") (pintype "passive"))
      (node (ref "IN-") (pin "P$1") (pinfunction "1_P$1") (pintype "bidirectional"))
      (node (ref "J1") (pin "1") (pinfunction "GND_1") (pintype "power_in"))
      (node (ref "J1") (pin "12") (pinfunction "GND_12") (pintype "power_in"))
      (node (ref "J1") (pin "S1") (pinfunction "SHIELD_S1") (pintype "passive"))
      (node (ref "J1") (pin "S2") (pinfunction "SHIELD_S2") (pintype "passive"))
      (node (ref "J1") (pin "S3") (pinfunction "SHIELD_S3") (pintype "passive"))
      (node (ref "J1") (pin "S4") (pinfunction "SHIELD_S4") (pintype "passive"))
      (node (ref "J1") (pin "S5") (pinfunction "SHIELD_S5") (pintype "passive"))
      (node (ref "J1") (pin "S6") (pinfunction "SHIELD_S6") (pintype "passive"))
      (node (ref "R34") (pin "1") (pinfunction "1_1") (pintype "passive"))
      (node (ref "R55") (pin "1") (pinfunction "1_1") (pintype "passive"))
      (node (ref "R56") (pin "1") (pinfunction "1_1") (pintype "passive"))
      (node (ref "RSENSE") (pin "1") (pinfunction "1_1") (pintype "passive"))
      (node (ref "U10") (pin "5") (pinfunction "GND_5") (pintype "bidirectional"))
      (node (ref "U9") (pin "2") (pinfunction "GND_2_2") (pintype "power_in"))
      (node (ref "U9") (pin "3") (pinfunction "GND_3") (pintype "power_in"))
    )
    (net (code "19") (name "/IN+") (class "Default")
      (node (ref "C36") (pin "2") (pinfunction "2_2") (pintype "passive"))
      (node (ref "C56") (pin "1") (pinfunction "1_1") (pintype "passive"))
      (node (ref "D3") (pin "2") (pinfunction "2_2") (pintype "bidirectional"))
      (node (ref "IN+") (pin "P$1") (pinfunction "1_P$1") (pintype "bidirectional"))
      (node (ref "J1") (pin "11") (pinfunction "VBUS_11") (pintype "power_in"))
      (node (ref "J1") (pin "2") (pinfunction "VBUS_2") (pintype "power_in"))
      (node (ref "PTC1") (pin "2") (pinfunction "2_2") (pintype "passive"))
      (node (ref "R47") (pin "1") (pinfunction "1_1") (pintype "passive"))
      (node (ref "R51") (pin "1") (pinfunction "1_1") (pintype "passive"))
      (node (ref "R62") (pin "2") (pinfunction "2_2") (pintype "passive"))
    )
    (net (code "20") (name "/ISENSE") (class "Default")
      (node (ref "TP4") (pin "1") (pinfunction "1_1") (pintype "passive"))
      (node (ref "U4") (pin "3") (pinfunction "OUT_3") (pintype "output"))
    )
    (net (code "21") (name "/MISO") (class "Default")
      (node (ref "R24") (pin "1") (pinfunction "1_1") (pintype "passive"))
    )
    (net (code "22") (name "/MOSI") (class "Default")
      (node (ref "R17") (pin "1") (pinfunction "1_1") (pintype "passive"))
    )
    (net (code "23") (name "/PEDAL") (class "Default")
      (node (ref "OP1") (pin "4") (pinfunction "COL_4") (pintype "passive"))
      (node (ref "R19") (pin "1") (pinfunction "1_1") (pintype "passive"))
      (node (ref "R99") (pin "1") (pinfunction "1_1") (pintype "passive"))
      (node (ref "TP5") (pin "1") (pinfunction "1_1") (pintype "passive"))
    )
    (net (code "24") (name "/PEDAL+") (class "Default")
      (node (ref "K1") (pin "2") (pinfunction "P$2_2") (pintype "bidirectional"))
      (node (ref "L3") (pin "1") (pinfunction "1_1") (pintype "passive"))
    )
    (net (code "25") (name "/PEDAL-") (class "Default")
      (node (ref "K1") (pin "1") (pinfunction "P$1_1") (pintype "bidirectional"))
      (node (ref "L4") (pin "1") (pinfunction "1_1") (pintype "passive"))
    )
    (net (code "26") (name "/PEDAL_IP") (class "Default")
      (node (ref "U6") (pin "4") (pinfunction "O_4") (pintype "output"))
    )
    (net (code "27") (name "/PUSH") (class "Default")
      (node (ref "R65") (pin "1") (pinfunction "1_1") (pintype "passive"))
      (node (ref "TP9") (pin "1") (pinfunction "1_1") (pintype "passive"))
      (node (ref "U6") (pin "5") (pinfunction "I_5") (pintype "input"))
    )
    (net (code "28") (name "/PUSH_FILT") (class "Default")
      (node (ref "U6") (pin "8") (pinfunction "O_8") (pintype "output"))
    )
    (net (code "29") (name "/QSPI_SCLK") (class "Default")
      (node (ref "IC1") (pin "6") (pinfunction "CLK_6") (pintype "bidirectional"))
      (node (ref "J2") (pin "52") (pinfunction "QSPI_SCLK_52") (pintype "bidirectional"))
    )
    (net (code "30") (name "/QSPI_SD0") (class "Default")
      (node (ref "IC1") (pin "2") (pinfunction "DO(IO1)_2") (pintype "bidirectional"))
      (node (ref "J2") (pin "53") (pinfunction "QSPI_SD0_53") (pintype "bidirectional"))
    )
    (net (code "31") (name "/QSPI_SD1") (class "Default")
      (node (ref "IC1") (pin "5") (pinfunction "DI(IO0)_5") (pintype "bidirectional"))
      (node (ref "J2") (pin "55") (pinfunction "QSPI_SD1_55") (pintype "bidirectional"))
    )
    (net (code "32") (name "/QSPI_SD2") (class "Default")
      (node (ref "IC1") (pin "3") (pinfunction "/WP_(IO2)_3") (pintype "bidirectional"))
      (node (ref "J2") (pin "54") (pinfunction "QSPI_SD2_54") (pintype "bidirectional"))
    )
    (net (code "33") (name "/QSPI_SD3") (class "Default")
      (node (ref "IC1") (pin "7") (pinfunction "/HOLD_OR_/RESET_(IO3)_7") (pintype "bidirectional"))
      (node (ref "J2") (pin "51") (pinfunction "QSPI_SD3_51") (pintype "bidirectional"))
    )
    (net (code "34") (name "/QSPI_SS") (class "Default")
      (node (ref "IC1") (pin "1") (pinfunction "/CS_1") (pintype "bidirectional"))
      (node (ref "J2") (pin "56") (pinfunction "QSPI_SS_N_56") (pintype "bidirectional"))
      (node (ref "R15") (pin "1") (pinfunction "1_1") (pintype "passive"))
    )
    (net (code "35") (name "/ROTA") (class "Default")
      (node (ref "C23") (pin "2") (pinfunction "2_2") (pintype "passive"))
      (node (ref "R53") (pin "1") (pinfunction "1_1") (pintype "passive"))
      (node (ref "S1") (pin "A") (pinfunction "A_A") (pintype "bidirectional"))
      (node (ref "U3") (pin "5") (pinfunction "I_5") (pintype "input"))
    )
    (net (code "36") (name "/ROTA_FILT") (class "Default")
      (node (ref "U3") (pin "4") (pinfunction "O_4") (pintype "output"))
    )
    (net (code "37") (name "/ROTB") (class "Default")
      (node (ref "C22") (pin "2") (pinfunction "2_2") (pintype "passive"))
      (node (ref "R52") (pin "1") (pinfunction "1_1") (pintype "passive"))
      (node (ref "S1") (pin "B") (pinfunction "B_B") (pintype "bidirectional"))
      (node (ref "U3") (pin "11") (pinfunction "I_11") (pintype "input"))
    )
    (net (code "38") (name "/ROTB_FILT") (class "Default")
      (node (ref "U3") (pin "8") (pinfunction "O_8") (pintype "output"))
    )
    (net (code "39") (name "/ROTPUSH") (class "Default")
      (node (ref "C24") (pin "2") (pinfunction "2_2") (pintype "passive"))
      (node (ref "R54") (pin "1") (pinfunction "1_1") (pintype "passive"))
      (node (ref "S1") (pin "SW+") (pinfunction "SW+_SW+") (pintype "bidirectional"))
      (node (ref "U3") (pin "1") (pinfunction "I_1") (pintype "input"))
    )
    (net (code "40") (name "/RPUSH_FILT") (class "Default")
      (node (ref "U3") (pin "12") (pinfunction "O_12") (pintype "output"))
    )
    (net (code "41") (name "/RST") (class "Default")
      (node (ref "J6") (pin "5") (pinfunction "RST_5") (pintype "bidirectional"))
      (node (ref "R21") (pin "2") (pinfunction "2_2") (pintype "passive"))
    )
    (net (code "42") (name "/RX-I") (class "Default")
      (node (ref "J4") (pin "P$3") (pinfunction "RXI_P$3") (pintype "bidirectional"))
    )
    (net (code "43") (name "/SAFETY_EN_DCDC") (class "Default")
      (node (ref "Q4") (pin "1") (pinfunction "G_1") (pintype "passive"))
      (node (ref "Q5") (pin "3") (pinfunction "D_3") (pintype "passive"))
      (node (ref "R27") (pin "1") (pinfunction "1_1") (pintype "passive"))
      (node (ref "R42") (pin "2") (pinfunction "2_2") (pintype "passive"))
    )
    (net (code "44") (name "/SCK") (class "Default")
      (node (ref "R14") (pin "1") (pinfunction "1_1") (pintype "passive"))
    )
    (net (code "45") (name "/SCL") (class "Default")
      (node (ref "TP7") (pin "1") (pinfunction "1_1") (pintype "passive"))
      (node (ref "U1") (pin "5") (pinfunction "SCL_5") (pintype "bidirectional"))
    )
    (net (code "46") (name "/SDA") (class "Default")
      (node (ref "L6") (pin "2") (pinfunction "2_2") (pintype "passive"))
      (node (ref "TP6") (pin "1") (pinfunction "1_1") (pintype "passive"))
      (node (ref "U1") (pin "4") (pinfunction "SDA_4") (pintype "bidirectional"))
    )
    (net (code "47") (name "/SEL") (class "Default")
      (node (ref "K1") (pin "3") (pinfunction "P$3_3") (pintype "bidirectional"))
    )
    (net (code "48") (name "/SPARE") (class "Default")
      (node (ref "C9") (pin "1") (pinfunction "1_1") (pintype "passive"))
      (node (ref "R18") (pin "2") (pinfunction "2_2") (pintype "passive"))
      (node (ref "R99") (pin "2") (pinfunction "2_2") (pintype "passive"))
      (node (ref "U6") (pin "1") (pinfunction "I_1") (pintype "input"))
    )
    (net (code "49") (name "/SPARE2") (class "Default")
      (node (ref "R38") (pin "1") (pinfunction "1_1") (pintype "passive"))
    )
    (net (code "50") (name "/SS") (class "Default")
      (node (ref "R29") (pin "1") (pinfunction "1_1") (pintype "passive"))
    )
    (net (code "51") (name "/SWCLK") (class "Default")
      (node (ref "J2") (pin "24") (pinfunction "SWCLK_24") (pintype "bidirectional"))
    )
    (net (code "52") (name "/SWDIO") (class "Default")
      (node (ref "J2") (pin "25") (pinfunction "SWDIO_25") (pintype "bidirectional"))
    )
    (net (code "53") (name "/TX-O") (class "Default")
      (node (ref "J4") (pin "P$2") (pinfunction "TXO_P$2") (pintype "bidirectional"))
    )
    (net (code "54") (name "/USB_D+") (class "Default")
      (node (ref "D4") (pin "2") (pinfunction "CATHODE_2_2") (pintype "bidirectional"))
      (node (ref "J1") (pin "6") (pinfunction "D+_6") (pintype "passive"))
      (node (ref "J1") (pin "7") (pinfunction "D+_7") (pintype "passive"))
    )
    (net (code "55") (name "/USB_D-") (class "Default")
      (node (ref "D4") (pin "1") (pinfunction "CATHODE_1_1") (pintype "bidirectional"))
      (node (ref "J1") (pin "5") (pinfunction "D-_5") (pintype "passive"))
      (node (ref "J1") (pin "8") (pinfunction "D-_8") (pintype "passive"))
    )
    (net (code "56") (name "/USB_DM") (class "Default")
      (node (ref "J2") (pin "46") (pinfunction "USB_DM_46") (pintype "bidirectional"))
    )
    (net (code "57") (name "/USB_DP") (class "Default")
      (node (ref "J2") (pin "47") (pinfunction "USB_DP_47") (pintype "bidirectional"))
    )
    (net (code "58") (name "/VBUS_SENSE") (class "Default")
      (node (ref "C58") (pin "2") (pinfunction "2_2") (pintype "passive"))
      (node (ref "D7") (pin "3") (pinfunction "AC_3") (pintype "passive"))
      (node (ref "R50") (pin "1") (pinfunction "1_1") (pintype "passive"))
      (node (ref "R51") (pin "2") (pinfunction "2_2") (pintype "passive"))
    )
    (net (code "59") (name "/VIN_ALARM") (class "Default")
      (node (ref "TP10") (pin "1") (pinfunction "1_1") (pintype "passive"))
      (node (ref "U6") (pin "10") (pinfunction "O_10") (pintype "output"))
    )
    (net (code "60") (name "/VISENSE") (class "Default")
      (node (ref "R30") (pin "1") (pinfunction "1_1") (pintype "passive"))
    )
    (net (code "61") (name "/VOSEN") (class "Default")
      (node (ref "C13") (pin "2") (pinfunction "2_2") (pintype "passive"))
      (node (ref "D2") (pin "3") (pinfunction "AC_3") (pintype "passive"))
      (node (ref "R36") (pin "1") (pinfunction "1_1") (pintype "passive"))
      (node (ref "R37") (pin "2") (pinfunction "2_2") (pintype "passive"))
      (node (ref "TP3") (pin "1") (pinfunction "1_1") (pintype "passive"))
    )
    (net (code "62") (name "/VOUT") (class "Default")
      (node (ref "D8") (pin "C") (pinfunction "K_C") (pintype "bidirectional"))
      (node (ref "K1") (pin "5") (pinfunction "P$5_5") (pintype "bidirectional"))
      (node (ref "K1") (pin "7") (pinfunction "P$6_7") (pintype "bidirectional"))
      (node (ref "R1") (pin "2") (pinfunction "2_2") (pintype "passive"))
      (node (ref "R12") (pin "2") (pinfunction "2_2") (pintype "passive"))
      (node (ref "R37") (pin "1") (pinfunction "1_1") (pintype "passive"))
      (node (ref "TP11") (pin "1") (pinfunction "1_1") (pintype "passive"))
    )
    (net (code "63") (name "/VO_TPS") (class "Default")
      (node (ref "C19") (pin "2") (pinfunction "2_2") (pintype "passive"))
      (node (ref "C34") (pin "2") (pinfunction "2_2") (pintype "passive"))
      (node (ref "C39") (pin "1") (pinfunction "1_1") (pintype "passive"))
      (node (ref "C40") (pin "1") (pinfunction "1_1") (pintype "passive"))
      (node (ref "C41") (pin "1") (pinfunction "1_1") (pintype "passive"))
      (node (ref "C42") (pin "1") (pinfunction "1_1") (pintype "passive"))
      (node (ref "C43") (pin "1") (pinfunction "1_1") (pintype "passive"))
      (node (ref "L2") (pin "2") (pinfunction "2_2") (pintype "passive"))
      (node (ref "R11") (pin "2") (pinfunction "2_2") (pintype "passive"))
      (node (ref "R12") (pin "1") (pinfunction "1_1") (pintype "passive"))
      (node (ref "TP14") (pin "1") (pinfunction "1_1") (pintype "passive"))
      (node (ref "U4") (pin "5") (pinfunction "RS+_5") (pintype "power_in"))
    )
    (net (code "64") (name "/XIN") (class "Default")
      (node (ref "C45") (pin "2") (pinfunction "2_2") (pintype "passive"))
      (node (ref "J2") (pin "20") (pinfunction "XIN_20") (pintype "bidirectional"))
      (node (ref "Y1") (pin "1") (pinfunction "1_1") (pintype "bidirectional"))
    )
    (net (code "65") (name "/XOUT") (class "Default")
      (node (ref "J2") (pin "21") (pinfunction "XOUT_21") (pintype "bidirectional"))
      (node (ref "R16") (pin "1") (pinfunction "1_1") (pintype "passive"))
    )
    (net (code "66") (name "1v1") (class "Default")
      (node (ref "C16") (pin "2") (pinfunction "2_2") (pintype "passive"))
      (node (ref "C27") (pin "2") (pinfunction "2_2") (pintype "passive"))
      (node (ref "C32") (pin "1") (pinfunction "1_1") (pintype "passive"))
      (node (ref "J2") (pin "23") (pinfunction "DVDD_1_23") (pintype "bidirectional"))
      (node (ref "J2") (pin "45") (pinfunction "VREG_VOUT_45") (pintype "bidirectional"))
      (node (ref "J2") (pin "50") (pinfunction "DVDD_2_50") (pintype "bidirectional"))
    )
    (net (code "67") (name "3V3MCU") (class "Default")
      (node (ref "C12") (pin "2") (pinfunction "2_2") (pintype "passive"))
      (node (ref "C15") (pin "1") (pinfunction "1_1") (pintype "passive"))
      (node (ref "C2") (pin "2") (pinfunction "2_2") (pintype "passive"))
      (node (ref "C20") (pin "2") (pinfunction "2_2") (pintype "passive"))
      (node (ref "C25") (pin "2") (pinfunction "2_2") (pintype "passive"))
      (node (ref "C26") (pin "1") (pinfunction "1_1") (pintype "passive"))
      (node (ref "C3") (pin "2") (pinfunction "2_2") (pintype "passive"))
      (node (ref "C31") (pin "1") (pinfunction "1_1") (pintype "passive"))
      (node (ref "C33") (pin "2") (pinfunction "2_2") (pintype "passive"))
      (node (ref "C4") (pin "2") (pinfunction "2_2") (pintype "passive"))
      (node (ref "C5") (pin "2") (pinfunction "2_2") (pintype "passive"))
      (node (ref "C50") (pin "2") (pinfunction "2_2") (pintype "passive"))
      (node (ref "C52") (pin "2") (pinfunction "2_2") (pintype "passive"))
      (node (ref "C53") (pin "2") (pinfunction "2_2") (pintype "passive"))
      (node (ref "C57") (pin "2") (pinfunction "2_2") (pintype "passive"))
      (node (ref "C59") (pin "2") (pinfunction "2_2") (pintype "passive"))
      (node (ref "C6") (pin "2") (pinfunction "2_2") (pintype "passive"))
      (node (ref "C62") (pin "2") (pinfunction "2_2") (pintype "passive"))
      (node (ref "C7") (pin "2") (pinfunction "2_2") (pintype "passive"))
      (node (ref "C8") (pin "2") (pinfunction "2_2") (pintype "passive"))
      (node (ref "D2") (pin "2") (pinfunction "C_2") (pintype "passive"))
      (node (ref "D7") (pin "2") (pinfunction "C_2") (pintype "passive"))
      (node (ref "IC1") (pin "8") (pinfunction "VCC_8") (pintype "bidirectional"))
      (node (ref "J2") (pin "1") (pinfunction "IOVDD_1_1") (pintype "bidirectional"))
      (node (ref "J2") (pin "10") (pinfunction "IOVDD_2_10") (pintype "bidirectional"))
      (node (ref "J2") (pin "22") (pinfunction "IOVDD_3_22") (pintype "bidirectional"))
      (node (ref "J2") (pin "33") (pinfunction "IOVDD_4_33") (pintype "bidirectional"))
      (node (ref "J2") (pin "42") (pinfunction "IOVDD_5_42") (pintype "bidirectional"))
      (node (ref "J2") (pin "44") (pinfunction "VREG_VIN_44") (pintype "bidirectional"))
      (node (ref "J2") (pin "48") (pinfunction "USB_VDD_48") (pintype "bidirectional"))
      (node (ref "J2") (pin "49") (pinfunction "IOVDD_6_49") (pintype "bidirectional"))
      (node (ref "J6") (pin "2") (pinfunction "VCC_2") (pintype "bidirectional"))
      (node (ref "K1") (pin "4") (pinfunction "P$4_4") (pintype "bidirectional"))
      (node (ref "L1") (pin "2") (pinfunction "2_2") (pintype "bidirectional"))
      (node (ref "R13") (pin "2") (pinfunction "2_2") (pintype "passive"))
      (node (ref "R15") (pin "2") (pinfunction "2_2") (pintype "passive"))
      (node (ref "R19") (pin "2") (pinfunction "2_2") (pintype "passive"))
      (node (ref "R28") (pin "1") (pinfunction "1_1") (pintype "passive"))
      (node (ref "R35") (pin "1") (pinfunction "1_1") (pintype "passive"))
      (node (ref "R52") (pin "2") (pinfunction "2_2") (pintype "passive"))
      (node (ref "R53") (pin "2") (pinfunction "2_2") (pintype "passive"))
      (node (ref "R54") (pin "2") (pinfunction "2_2") (pintype "passive"))
      (node (ref "R66") (pin "1") (pinfunction "1_1") (pintype "passive"))
      (node (ref "U3") (pin "14") (pinfunction "VCC_14") (pintype "power_in"))
      (node (ref "U6") (pin "14") (pinfunction "VCC_14") (pintype "power_in"))
      (node (ref "U7") (pin "1") (pinfunction "VCC_1") (pintype "bidirectional"))
    )
    (net (code "68") (name "GND") (class "Default")
      (node (ref "C1") (pin "1") (pinfunction "1_1") (pintype "passive"))
      (node (ref "C10") (pin "1") (pinfunction "1_1") (pintype "passive"))
      (node (ref "C11") (pin "1") (pinfunction "1_1") (pintype "passive"))
      (node (ref "C12") (pin "1") (pinfunction "1_1") (pintype "passive"))
      (node (ref "C13") (pin "1") (pinfunction "1_1") (pintype "passive"))
      (node (ref "C14") (pin "1") (pinfunction "1_1") (pintype "passive"))
      (node (ref "C15") (pin "2") (pinfunction "2_2") (pintype "passive"))
      (node (ref "C16") (pin "1") (pinfunction "1_1") (pintype "passive"))
      (node (ref "C17") (pin "2") (pinfunction "2_2") (pintype "passive"))
      (node (ref "C18") (pin "2") (pinfunction "2_2") (pintype "passive"))
      (node (ref "C2") (pin "1") (pinfunction "1_1") (pintype "passive"))
      (node (ref "C20") (pin "1") (pinfunction "1_1") (pintype "passive"))
      (node (ref "C21") (pin "2") (pinfunction "2_2") (pintype "passive"))
      (node (ref "C22") (pin "1") (pinfunction "1_1") (pintype "passive"))
      (node (ref "C23") (pin "1") (pinfunction "1_1") (pintype "passive"))
      (node (ref "C24") (pin "1") (pinfunction "1_1") (pintype "passive"))
      (node (ref "C25") (pin "1") (pinfunction "1_1") (pintype "passive"))
      (node (ref "C26") (pin "2") (pinfunction "2_2") (pintype "passive"))
      (node (ref "C27") (pin "1") (pinfunction "1_1") (pintype "passive"))
      (node (ref "C28") (pin "1") (pinfunction "1_1") (pintype "passive"))
      (node (ref "C3") (pin "1") (pinfunction "1_1") (pintype "passive"))
      (node (ref "C30") (pin "1") (pinfunction "1_1") (pintype "passive"))
      (node (ref "C31") (pin "2") (pinfunction "2_2") (pintype "passive"))
      (node (ref "C32") (pin "2") (pinfunction "2_2") (pintype "passive"))
      (node (ref "C33") (pin "1") (pinfunction "1_1") (pintype "passive"))
      (node (ref "C34") (pin "1") (pinfunction "1_1") (pintype "passive"))
      (node (ref "C35") (pin "2") (pinfunction "2_2") (pintype "passive"))
      (node (ref "C36") (pin "1") (pinfunction "1_1") (pintype "passive"))
      (node (ref "C38") (pin "1") (pinfunction "1_1") (pintype "passive"))
      (node (ref "C39") (pin "2") (pinfunction "2_2") (pintype "passive"))
      (node (ref "C4") (pin "1") (pinfunction "1_1") (pintype "passive"))
      (node (ref "C40") (pin "2") (pinfunction "2_2") (pintype "passive"))
      (node (ref "C41") (pin "2") (pinfunction "2_2") (pintype "passive"))
      (node (ref "C42") (pin "2") (pinfunction "2_2") (pintype "passive"))
      (node (ref "C44") (pin "2") (pinfunction "2_2") (pintype "passive"))
      (node (ref "C45") (pin "1") (pinfunction "1_1") (pintype "passive"))
      (node (ref "C46") (pin "1") (pinfunction "1_1") (pintype "passive"))
      (node (ref "C47") (pin "1") (pinfunction "1_1") (pintype "passive"))
      (node (ref "C48") (pin "1") (pinfunction "1_1") (pintype "passive"))
      (node (ref "C49") (pin "1") (pinfunction "1_1") (pintype "passive"))
      (node (ref "C5") (pin "1") (pinfunction "1_1") (pintype "passive"))
      (node (ref "C50") (pin "1") (pinfunction "1_1") (pintype "passive"))
      (node (ref "C53") (pin "1") (pinfunction "1_1") (pintype "passive"))
      (node (ref "C54") (pin "1") (pinfunction "1_1") (pintype "passive"))
      (node (ref "C57") (pin "1") (pinfunction "1_1") (pintype "passive"))
      (node (ref "C58") (pin "1") (pinfunction "1_1") (pintype "passive"))
      (node (ref "C59") (pin "1") (pinfunction "1_1") (pintype "passive"))
      (node (ref "C6") (pin "1") (pinfunction "1_1") (pintype "passive"))
      (node (ref "C60") (pin "1") (pinfunction "1_1") (pintype "passive"))
      (node (ref "C61") (pin "1") (pinfunction "1_1") (pintype "passive"))
      (node (ref "C62") (pin "1") (pinfunction "1_1") (pintype "passive"))
      (node (ref "C63") (pin "1") (pinfunction "1_1") (pintype "passive"))
      (node (ref "C64") (pin "1") (pinfunction "1_1") (pintype "passive"))
      (node (ref "C7") (pin "1") (pinfunction "1_1") (pintype "passive"))
      (node (ref "C8") (pin "1") (pinfunction "1_1") (pintype "passive"))
      (node (ref "C9") (pin "2") (pinfunction "2_2") (pintype "passive"))
      (node (ref "D2") (pin "1") (pinfunction "A_1") (pintype "passive"))
      (node (ref "D3") (pin "1") (pinfunction "1_1") (pintype "bidirectional"))
      (node (ref "D4") (pin "3") (pinfunction "COMMON_CATHODE_3") (pintype "bidirectional"))
      (node (ref "D7") (pin "1") (pinfunction "A_1") (pintype "passive"))
      (node (ref "D8") (pin "A") (pinfunction "A_A") (pintype "bidirectional"))
      (node (ref "IC1") (pin "4") (pinfunction "GND_4") (pintype "bidirectional"))
      (node (ref "IC3") (pin "7") (pinfunction "GND_7") (pintype "bidirectional"))
      (node (ref "IC3") (pin "9") (pinfunction "EP_9") (pintype "bidirectional"))
      (node (ref "J2") (pin "19") (pinfunction "TESTEN_19") (pintype "bidirectional"))
      (node (ref "J2") (pin "57") (pinfunction "GND_57") (pintype "bidirectional"))
      (node (ref "J4") (pin "P$5") (pinfunction "CTS_P$5") (pintype "bidirectional"))
      (node (ref "J4") (pin "P$6") (pinfunction "GND_P$6") (pintype "bidirectional"))
      (node (ref "J6") (pin "1") (pinfunction "GND_1") (pintype "bidirectional"))
      (node (ref "K1") (pin "8") (pinfunction "P$7_8") (pintype "bidirectional"))
      (node (ref "K1") (pin "9") (pinfunction "P$8_9") (pintype "bidirectional"))
      (node (ref "OP1") (pin "3") (pinfunction "EMIT_3") (pintype "passive"))
      (node (ref "PS1") (pin "4") (pinfunction "GND_4") (pintype "bidirectional"))
      (node (ref "Q1") (pin "2") (pinfunction "S_2") (pintype "passive"))
      (node (ref "Q2") (pin "2") (pinfunction "S_2") (pintype "passive"))
      (node (ref "Q5") (pin "2") (pinfunction "S_2") (pintype "passive"))
      (node (ref "R18") (pin "1") (pinfunction "1_1") (pintype "passive"))
      (node (ref "R22") (pin "2") (pinfunction "2_2") (pintype "passive"))
      (node (ref "R3") (pin "1") (pinfunction "1_1") (pintype "passive"))
      (node (ref "R32") (pin "2") (pinfunction "2_2") (pintype "passive"))
      (node (ref "R36") (pin "2") (pinfunction "2_2") (pintype "passive"))
      (node (ref "R42") (pin "1") (pinfunction "1_1") (pintype "passive"))
      (node (ref "R43") (pin "1") (pinfunction "1_1") (pintype "passive"))
      (node (ref "R44") (pin "1") (pinfunction "1_1") (pintype "passive"))
      (node (ref "R49") (pin "1") (pinfunction "1_1") (pintype "passive"))
      (node (ref "R50") (pin "2") (pinfunction "2_2") (pintype "passive"))
      (node (ref "R57") (pin "2") (pinfunction "2_2") (pintype "passive"))
      (node (ref "R58") (pin "2") (pinfunction "2_2") (pintype "passive"))
      (node (ref "R59") (pin "1") (pinfunction "1_1") (pintype "passive"))
      (node (ref "RSENSE") (pin "2") (pinfunction "2_2") (pintype "passive"))
      (node (ref "S1") (pin "C") (pinfunction "C_C") (pintype "bidirectional"))
      (node (ref "S1") (pin "SW-") (pinfunction "SW-_SW-") (pintype "bidirectional"))
      (node (ref "S2") (pin "2") (pinfunction "2_2") (pintype "passive"))
      (node (ref "TP12") (pin "1") (pinfunction "1_1") (pintype "passive"))
      (node (ref "U1") (pin "2") (pinfunction "VSS_2") (pintype "bidirectional"))
      (node (ref "U1") (pin "6") (pinfunction "AO_6") (pintype "bidirectional"))
      (node (ref "U3") (pin "7") (pinfunction "GND_7") (pintype "power_in"))
      (node (ref "U4") (pin "1") (pinfunction "GND_1") (pintype "passive"))
      (node (ref "U4") (pin "2") (pinfunction "GND_2_2") (pintype "passive"))
      (node (ref "U6") (pin "7") (pinfunction "GND_7") (pintype "power_in"))
      (node (ref "U7") (pin "10") (pinfunction "A1_10") (pintype "bidirectional"))
      (node (ref "U7") (pin "16") (pinfunction "GND_16") (pintype "bidirectional"))
      (node (ref "U7") (pin "7") (pinfunction "A2_7") (pintype "bidirectional"))
      (node (ref "U7") (pin "8") (pinfunction "~{G}_8") (pintype "bidirectional"))
      (node (ref "U7") (pin "9") (pinfunction "A0_9") (pintype "bidirectional"))
    )
    (net (code "69") (name "IN_OVC") (class "Default")
      (node (ref "Q5") (pin "1") (pinfunction "G_1") (pintype "passive"))
      (node (ref "R48") (pin "2") (pinfunction "2_2") (pintype "passive"))
      (node (ref "R49") (pin "2") (pinfunction "2_2") (pintype "passive"))
    )
    (net (code "70") (name "Net-(BZ1-+)") (class "Default")
      (node (ref "BZ1") (pin "1") (pinfunction "+_1") (pintype "passive"))
      (node (ref "C61") (pin "2") (pinfunction "2_2") (pintype "passive"))
      (node (ref "L7") (pin "2") (pinfunction "2_2") (pintype "passive"))
      (node (ref "R61") (pin "2") (pinfunction "2_2") (pintype "passive"))
    )
    (net (code "71") (name "Net-(BZ1--)") (class "Default")
      (node (ref "BZ1") (pin "2") (pinfunction "-_2") (pintype "passive"))
      (node (ref "D6") (pin "3") (pinfunction "AC_3") (pintype "passive"))
      (node (ref "LS1") (pin "2") (pinfunction "-_2") (pintype "bidirectional"))
      (node (ref "Q1") (pin "3") (pinfunction "D_3") (pintype "passive"))
      (node (ref "R61") (pin "1") (pinfunction "1_1") (pintype "passive"))
    )
    (net (code "72") (name "Net-(C10-Pad2)") (class "Default")
      (node (ref "C10") (pin "2") (pinfunction "2_2") (pintype "passive"))
      (node (ref "R13") (pin "1") (pinfunction "1_1") (pintype "passive"))
      (node (ref "R65") (pin "2") (pinfunction "2_2") (pintype "passive"))
      (node (ref "S2") (pin "4") (pinfunction "4_4") (pintype "passive"))
    )
    (net (code "73") (name "Net-(C37-Pad1)") (class "Default")
      (node (ref "C37") (pin "1") (pinfunction "1_1") (pintype "passive"))
      (node (ref "R44") (pin "2") (pinfunction "2_2") (pintype "passive"))
    )
    (net (code "74") (name "Net-(C46-Pad2)") (class "Default")
      (node (ref "C46") (pin "2") (pinfunction "2_2") (pintype "passive"))
      (node (ref "R16") (pin "2") (pinfunction "2_2") (pintype "passive"))
      (node (ref "Y1") (pin "2") (pinfunction "2_2") (pintype "bidirectional"))
    )
    (net (code "75") (name "Net-(D6-C)") (class "Default")
      (node (ref "C44") (pin "1") (pinfunction "1_1") (pintype "passive"))
      (node (ref "D6") (pin "2") (pinfunction "C_2") (pintype "passive"))
      (node (ref "LS1") (pin "3") (pinfunction "DUMMY_3") (pintype "bidirectional"))
    )
    (net (code "76") (name "Net-(IC3-BST)") (class "Default")
      (node (ref "C29") (pin "1") (pinfunction "1_1") (pintype "passive"))
      (node (ref "IC3") (pin "1") (pinfunction "BST_1") (pintype "bidirectional"))
    )
    (net (code "77") (name "Net-(IC3-COMP)") (class "Default")
      (node (ref "C37") (pin "2") (pinfunction "2_2") (pintype "passive"))
      (node (ref "C38") (pin "2") (pinfunction "2_2") (pintype "passive"))
      (node (ref "IC3") (pin "6") (pinfunction "COMP_6") (pintype "bidirectional"))
    )
    (net (code "78") (name "Net-(IC3-FB)") (class "Default")
      (node (ref "C19") (pin "1") (pinfunction "1_1") (pintype "passive"))
      (node (ref "IC3") (pin "5") (pinfunction "FB_5") (pintype "bidirectional"))
      (node (ref "R10") (pin "2") (pinfunction "2_2") (pintype "passive"))
      (node (ref "R11") (pin "1") (pinfunction "1_1") (pintype "passive"))
      (node (ref "R3") (pin "2") (pinfunction "2_2") (pintype "passive"))
      (node (ref "R4") (pin "2") (pinfunction "2_2") (pintype "passive"))
      (node (ref "R40") (pin "2") (pinfunction "2_2") (pintype "passive"))
      (node (ref "R45") (pin "2") (pinfunction "2_2") (pintype "passive"))
      (node (ref "R5") (pin "2") (pinfunction "2_2") (pintype "passive"))
      (node (ref "R6") (pin "2") (pinfunction "2_2") (pintype "passive"))
      (node (ref "R7") (pin "2") (pinfunction "2_2") (pintype "passive"))
      (node (ref "R8") (pin "2") (pinfunction "2_2") (pintype "passive"))
      (node (ref "R9") (pin "2") (pinfunction "2_2") (pintype "passive"))
    )
    (net (code "79") (name "Net-(IC3-SS)") (class "Default")
      (node (ref "C30") (pin "2") (pinfunction "2_2") (pintype "passive"))
      (node (ref "IC3") (pin "4") (pinfunction "SS_4") (pintype "bidirectional"))
    )
    (net (code "80") (name "Net-(IC3-SW)") (class "Default")
      (node (ref "C29") (pin "2") (pinfunction "2_2") (pintype "passive"))
      (node (ref "IC3") (pin "8") (pinfunction "SW_8") (pintype "bidirectional"))
      (node (ref "L2") (pin "1") (pinfunction "1_1") (pintype "passive"))
    )
    (net (code "81") (name "Net-(J4-VCC)") (class "Default")
      (node (ref "C1") (pin "2") (pinfunction "2_2") (pintype "passive"))
      (node (ref "J4") (pin "P$4") (pinfunction "VCC_P$4") (pintype "bidirectional"))
    )
    (net (code "82") (name "Net-(J6-DC)") (class "Default")
      (node (ref "J6") (pin "6") (pinfunction "DC_6") (pintype "bidirectional"))
      (node (ref "R24") (pin "2") (pinfunction "2_2") (pintype "passive"))
    )
    (net (code "83") (name "Net-(L3-Pad2)") (class "Default")
      (node (ref "L3") (pin "2") (pinfunction "2_2") (pintype "passive"))
      (node (ref "R26") (pin "1") (pinfunction "1_1") (pintype "passive"))
    )
    (net (code "84") (name "Net-(L4-Pad2)") (class "Default")
      (node (ref "L4") (pin "2") (pinfunction "2_2") (pintype "passive"))
      (node (ref "R22") (pin "1") (pinfunction "1_1") (pintype "passive"))
    )
    (net (code "85") (name "Net-(LED1-C)") (class "Default")
      (node (ref "LED1") (pin "K") (pinfunction "C_K") (pintype "passive"))
      (node (ref "Q2") (pin "3") (pinfunction "D_3") (pintype "passive"))
    )
    (net (code "86") (name "Net-(LED1-PadA)") (class "Default")
      (node (ref "LED1") (pin "A") (pinfunction "A_A") (pintype "passive"))
      (node (ref "R35") (pin "2") (pinfunction "2_2") (pintype "passive"))
    )
    (net (code "87") (name "Net-(OP1-A)") (class "Default")
      (node (ref "D5") (pin "A") (pinfunction "A_A") (pintype "passive"))
      (node (ref "OP1") (pin "1") (pinfunction "A_1") (pintype "passive"))
    )
    (net (code "88") (name "Net-(OP1-C)") (class "Default")
      (node (ref "OP1") (pin "2") (pinfunction "C_2") (pintype "passive"))
      (node (ref "R26") (pin "2") (pinfunction "2_2") (pintype "passive"))
    )
    (net (code "89") (name "Net-(PS1-BST)") (class "Default")
      (node (ref "C51") (pin "2") (pinfunction "2_2") (pintype "passive"))
      (node (ref "PS1") (pin "6") (pinfunction "BST_6") (pintype "bidirectional"))
    )
    (net (code "90") (name "Net-(PS1-SW)") (class "Default")
      (node (ref "C51") (pin "1") (pinfunction "1_1") (pintype "passive"))
      (node (ref "L1") (pin "1") (pinfunction "1_1") (pintype "bidirectional"))
      (node (ref "PS1") (pin "5") (pinfunction "SW_5") (pintype "bidirectional"))
    )
    (net (code "91") (name "Net-(Q1-G)") (class "Default")
      (node (ref "Q1") (pin "1") (pinfunction "G_1") (pintype "passive"))
      (node (ref "R46") (pin "2") (pinfunction "2_2") (pintype "passive"))
      (node (ref "R57") (pin "1") (pinfunction "1_1") (pintype "passive"))
    )
    (net (code "92") (name "Net-(Q2-G)") (class "Default")
      (node (ref "Q2") (pin "1") (pinfunction "G_1") (pintype "passive"))
      (node (ref "R31") (pin "2") (pinfunction "2_2") (pintype "passive"))
    )
    (net (code "93") (name "Net-(Q4-D)") (class "Default")
      (node (ref "Q4") (pin "3") (pinfunction "D_3") (pintype "passive"))
      (node (ref "R41") (pin "1") (pinfunction "1_1") (pintype "passive"))
    )
    (net (code "94") (name "Net-(R38-Pad2)") (class "Default")
      (node (ref "R38") (pin "2") (pinfunction "2_2") (pintype "passive"))
      (node (ref "TP1") (pin "1") (pinfunction "1_1") (pintype "passive"))
    )
    (net (code "95") (name "Net-(U3A-I)") (class "Default")
      (node (ref "C49") (pin "2") (pinfunction "2_2") (pintype "passive"))
      (node (ref "R25") (pin "2") (pinfunction "2_2") (pintype "passive"))
      (node (ref "U3") (pin "13") (pinfunction "I_13") (pintype "input"))
    )
    (net (code "96") (name "Net-(U3B-O)") (class "Default")
      (node (ref "R2") (pin "1") (pinfunction "1_1") (pintype "passive"))
      (node (ref "U3") (pin "10") (pinfunction "O_10") (pintype "output"))
    )
    (net (code "97") (name "Net-(U3C-I)") (class "Default")
      (node (ref "C47") (pin "2") (pinfunction "2_2") (pintype "passive"))
      (node (ref "R2") (pin "2") (pinfunction "2_2") (pintype "passive"))
      (node (ref "U3") (pin "9") (pinfunction "I_9") (pintype "input"))
    )
    (net (code "98") (name "Net-(U3D-O)") (class "Default")
      (node (ref "R25") (pin "1") (pinfunction "1_1") (pintype "passive"))
      (node (ref "U3") (pin "2") (pinfunction "O_2") (pintype "output"))
    )
    (net (code "99") (name "Net-(U3E-I)") (class "Default")
      (node (ref "C48") (pin "2") (pinfunction "2_2") (pintype "passive"))
      (node (ref "R20") (pin "2") (pinfunction "2_2") (pintype "passive"))
      (node (ref "U3") (pin "3") (pinfunction "I_3") (pintype "input"))
    )
    (net (code "100") (name "Net-(U3F-O)") (class "Default")
      (node (ref "R20") (pin "1") (pinfunction "1_1") (pintype "passive"))
      (node (ref "U3") (pin "6") (pinfunction "O_6") (pintype "output"))
    )
    (net (code "101") (name "Net-(U4-RS-)") (class "Default")
      (node (ref "C43") (pin "2") (pinfunction "2_2") (pintype "passive"))
      (node (ref "R1") (pin "1") (pinfunction "1_1") (pintype "passive"))
      (node (ref "U4") (pin "4") (pinfunction "RS-_4") (pintype "input"))
    )
    (net (code "102") (name "Net-(U6A-I)") (class "Default")
      (node (ref "R30") (pin "2") (pinfunction "2_2") (pintype "passive"))
      (node (ref "R58") (pin "1") (pinfunction "1_1") (pintype "passive"))
      (node (ref "U6") (pin "13") (pinfunction "I_13") (pintype "input"))
    )
    (net (code "103") (name "Net-(U6A-O)") (class "Default")
      (node (ref "R39") (pin "1") (pinfunction "1_1") (pintype "passive"))
      (node (ref "U6") (pin "12") (pinfunction "O_12") (pintype "output"))
    )
    (net (code "104") (name "Net-(U6B-I)") (class "Default")
      (node (ref "C54") (pin "2") (pinfunction "2_2") (pintype "passive"))
      (node (ref "R39") (pin "2") (pinfunction "2_2") (pintype "passive"))
      (node (ref "U6") (pin "11") (pinfunction "I_11") (pintype "input"))
    )
    (net (code "105") (name "Net-(U6C-I)") (class "Default")
      (node (ref "C14") (pin "2") (pinfunction "2_2") (pintype "passive"))
      (node (ref "R33") (pin "2") (pinfunction "2_2") (pintype "passive"))
      (node (ref "U6") (pin "9") (pinfunction "I_9") (pintype "input"))
    )
    (net (code "106") (name "Net-(U6D-O)") (class "Default")
      (node (ref "R23") (pin "1") (pinfunction "1_1") (pintype "passive"))
      (node (ref "U6") (pin "2") (pinfunction "O_2") (pintype "output"))
    )
    (net (code "107") (name "Net-(U6E-I)") (class "Default")
      (node (ref "C11") (pin "2") (pinfunction "2_2") (pintype "passive"))
      (node (ref "R23") (pin "2") (pinfunction "2_2") (pintype "passive"))
      (node (ref "U6") (pin "3") (pinfunction "I_3") (pintype "input"))
    )
    (net (code "108") (name "Net-(U6F-O)") (class "Default")
      (node (ref "R33") (pin "1") (pinfunction "1_1") (pintype "passive"))
      (node (ref "U6") (pin "6") (pinfunction "O_6") (pintype "output"))
    )
    (net (code "109") (name "Net-(U7-DRAIN0)") (class "Default")
      (node (ref "R8") (pin "1") (pinfunction "1_1") (pintype "passive"))
      (node (ref "U7") (pin "3") (pinfunction "DRAIN0_3") (pintype "bidirectional"))
    )
    (net (code "110") (name "Net-(U7-DRAIN1)") (class "Default")
      (node (ref "R7") (pin "1") (pinfunction "1_1") (pintype "passive"))
      (node (ref "U7") (pin "4") (pinfunction "DRAIN1_4") (pintype "bidirectional"))
    )
    (net (code "111") (name "Net-(U7-DRAIN2)") (class "Default")
      (node (ref "R6") (pin "1") (pinfunction "1_1") (pintype "passive"))
      (node (ref "U7") (pin "5") (pinfunction "DRAIN2_5") (pintype "bidirectional"))
    )
    (net (code "112") (name "Net-(U7-DRAIN3)") (class "Default")
      (node (ref "R5") (pin "1") (pinfunction "1_1") (pintype "passive"))
      (node (ref "U7") (pin "6") (pinfunction "DRAIN3_6") (pintype "bidirectional"))
    )
    (net (code "113") (name "Net-(U7-DRAIN4)") (class "Default")
      (node (ref "R45") (pin "1") (pinfunction "1_1") (pintype "passive"))
      (node (ref "U7") (pin "11") (pinfunction "DRAIN4_11") (pintype "bidirectional"))
    )
    (net (code "114") (name "Net-(U7-DRAIN5)") (class "Default")
      (node (ref "R40") (pin "1") (pinfunction "1_1") (pintype "passive"))
      (node (ref "U7") (pin "12") (pinfunction "DRAIN5_12") (pintype "bidirectional"))
    )
    (net (code "115") (name "Net-(U7-DRAIN6)") (class "Default")
      (node (ref "R10") (pin "1") (pinfunction "1_1") (pintype "passive"))
      (node (ref "U7") (pin "13") (pinfunction "DRAIN6_13") (pintype "bidirectional"))
    )
    (net (code "116") (name "Net-(U7-DRAIN7)") (class "Default")
      (node (ref "R9") (pin "1") (pinfunction "1_1") (pintype "passive"))
      (node (ref "U7") (pin "14") (pinfunction "DRAIN7_14") (pintype "bidirectional"))
    )
    (net (code "117") (name "Net-(U7-SCL)") (class "Default")
      (node (ref "L5") (pin "1") (pinfunction "1_1") (pintype "passive"))
      (node (ref "U7") (pin "15") (pinfunction "SCL_15") (pintype "bidirectional"))
    )
    (net (code "118") (name "Net-(U7-SDA)") (class "Default")
      (node (ref "L6") (pin "1") (pinfunction "1_1") (pintype "passive"))
      (node (ref "U7") (pin "2") (pinfunction "SDA_2") (pintype "bidirectional"))
    )
    (net (code "119") (name "Net-(U9-IN)") (class "Default")
      (node (ref "C55") (pin "2") (pinfunction "2_2") (pintype "passive"))
      (node (ref "R34") (pin "2") (pinfunction "2_2") (pintype "passive"))
      (node (ref "R59") (pin "2") (pinfunction "2_2") (pintype "passive"))
      (node (ref "U9") (pin "4") (pinfunction "IN_4") (pintype "input"))
    )
    (net (code "120") (name "Net-(U9-OUT)") (class "Default")
      (node (ref "R48") (pin "1") (pinfunction "1_1") (pintype "passive"))
      (node (ref "U9") (pin "5") (pinfunction "OUT_5") (pintype "output"))
    )
    (net (code "121") (name "Net-(U10-SEL)") (class "Default")
      (node (ref "R62") (pin "1") (pinfunction "1_1") (pintype "passive"))
      (node (ref "U10") (pin "11") (pinfunction "SEL_11") (pintype "bidirectional"))
    )
    (net (code "122") (name "Net-(U10-VIN)") (class "Default")
      (node (ref "R47") (pin "2") (pinfunction "2_2") (pintype "passive"))
      (node (ref "U10") (pin "2") (pinfunction "VIN_2") (pintype "bidirectional"))
    )
    (net (code "123") (name "VCC") (class "Default")
      (node (ref "C17") (pin "1") (pinfunction "1_1") (pintype "passive"))
      (node (ref "C18") (pin "1") (pinfunction "1_1") (pintype "passive"))
      (node (ref "C21") (pin "1") (pinfunction "1_1") (pintype "passive"))
      (node (ref "C28") (pin "2") (pinfunction "2_2") (pintype "passive"))
      (node (ref "C35") (pin "1") (pinfunction "1_1") (pintype "passive"))
      (node (ref "C60") (pin "2") (pinfunction "2_2") (pintype "passive"))
      (node (ref "C63") (pin "2") (pinfunction "2_2") (pintype "passive"))
      (node (ref "C64") (pin "2") (pinfunction "2_2") (pintype "passive"))
      (node (ref "D5") (pin "C") (pinfunction "K_C") (pintype "passive"))
      (node (ref "IC3") (pin "2") (pinfunction "VIN_2") (pintype "bidirectional"))
      (node (ref "L7") (pin "1") (pinfunction "1_1") (pintype "passive"))
      (node (ref "PS1") (pin "2") (pinfunction "EN_2") (pintype "bidirectional"))
      (node (ref "PS1") (pin "3") (pinfunction "VIN_3") (pintype "bidirectional"))
      (node (ref "PTC1") (pin "1") (pinfunction "1_1") (pintype "passive"))
      (node (ref "R41") (pin "2") (pinfunction "2_2") (pintype "passive"))
      (node (ref "U1") (pin "3") (pinfunction "VDD_3") (pintype "bidirectional"))
    )
    (net (code "124") (name "VCCIO") (class "Default")
      (node (ref "TP2") (pin "1") (pinfunction "1_1") (pintype "passive"))
    )
    (net (code "125") (name "unconnected-(D6-A-Pad1)") (class "Default")
      (node (ref "D6") (pin "1") (pinfunction "A_1") (pintype "passive"))
    )
    (net (code "126") (name "unconnected-(J2-GPIO0-Pad2)") (class "Default")
      (node (ref "J2") (pin "2") (pinfunction "GPIO0_2") (pintype "bidirectional"))
    )
    (net (code "127") (name "unconnected-(J2-GPIO1-Pad3)") (class "Default")
      (node (ref "J2") (pin "3") (pinfunction "GPIO1_3") (pintype "bidirectional"))
    )
    (net (code "128") (name "unconnected-(J2-GPIO2-Pad4)") (class "Default")
      (node (ref "J2") (pin "4") (pinfunction "GPIO2_4") (pintype "bidirectional"))
    )
    (net (code "129") (name "unconnected-(J2-GPIO3-Pad5)") (class "Default")
      (node (ref "J2") (pin "5") (pinfunction "GPIO3_5") (pintype "bidirectional"))
    )
    (net (code "130") (name "unconnected-(J2-GPIO4-Pad6)") (class "Default")
      (node (ref "J2") (pin "6") (pinfunction "GPIO4_6") (pintype "bidirectional"))
    )
    (net (code "131") (name "unconnected-(J2-GPIO5-Pad7)") (class "Default")
      (node (ref "J2") (pin "7") (pinfunction "GPIO5_7") (pintype "bidirectional"))
    )
    (net (code "132") (name "unconnected-(J2-GPIO6-Pad8)") (class "Default")
      (node (ref "J2") (pin "8") (pinfunction "GPIO6_8") (pintype "bidirectional"))
    )
    (net (code "133") (name "unconnected-(J2-GPIO7-Pad9)") (class "Default")
      (node (ref "J2") (pin "9") (pinfunction "GPIO7_9") (pintype "bidirectional"))
    )
    (net (code "134") (name "unconnected-(J2-GPIO8-Pad11)") (class "Default")
      (node (ref "J2") (pin "11") (pinfunction "GPIO8_11") (pintype "bidirectional"))
    )
    (net (code "135") (name "unconnected-(J2-GPIO9-Pad12)") (class "Default")
      (node (ref "J2") (pin "12") (pinfunction "GPIO9_12") (pintype "bidirectional"))
    )
    (net (code "136") (name "unconnected-(J2-GPIO10-Pad13)") (class "Default")
      (node (ref "J2") (pin "13") (pinfunction "GPIO10_13") (pintype "bidirectional"))
    )
    (net (code "137") (name "unconnected-(J2-GPIO11-Pad14)") (class "Default")
      (node (ref "J2") (pin "14") (pinfunction "GPIO11_14") (pintype "bidirectional"))
    )
    (net (code "138") (name "unconnected-(J2-GPIO12-Pad15)") (class "Default")
      (node (ref "J2") (pin "15") (pinfunction "GPIO12_15") (pintype "bidirectional"))
    )
    (net (code "139") (name "unconnected-(J2-GPIO13-Pad16)") (class "Default")
      (node (ref "J2") (pin "16") (pinfunction "GPIO13_16") (pintype "bidirectional"))
    )
    (net (code "140") (name "unconnected-(J2-GPIO14-Pad17)") (class "Default")
      (node (ref "J2") (pin "17") (pinfunction "GPIO14_17") (pintype "bidirectional"))
    )
    (net (code "141") (name "unconnected-(J2-GPIO15-Pad18)") (class "Default")
      (node (ref "J2") (pin "18") (pinfunction "GPIO15_18") (pintype "bidirectional"))
    )
    (net (code "142") (name "unconnected-(J2-GPIO16-Pad27)") (class "Default")
      (node (ref "J2") (pin "27") (pinfunction "GPIO16_27") (pintype "bidirectional"))
    )
    (net (code "143") (name "unconnected-(J2-GPIO17-Pad28)") (class "Default")
      (node (ref "J2") (pin "28") (pinfunction "GPIO17_28") (pintype "bidirectional"))
    )
    (net (code "144") (name "unconnected-(J2-GPIO18-Pad29)") (class "Default")
      (node (ref "J2") (pin "29") (pinfunction "GPIO18_29") (pintype "bidirectional"))
    )
    (net (code "145") (name "unconnected-(J2-GPIO19-Pad30)") (class "Default")
      (node (ref "J2") (pin "30") (pinfunction "GPIO19_30") (pintype "bidirectional"))
    )
    (net (code "146") (name "unconnected-(J2-GPIO20-Pad31)") (class "Default")
      (node (ref "J2") (pin "31") (pinfunction "GPIO20_31") (pintype "bidirectional"))
    )
    (net (code "147") (name "unconnected-(J2-GPIO21-Pad32)") (class "Default")
      (node (ref "J2") (pin "32") (pinfunction "GPIO21_32") (pintype "bidirectional"))
    )
    (net (code "148") (name "unconnected-(J2-GPIO22-Pad34)") (class "Default")
      (node (ref "J2") (pin "34") (pinfunction "GPIO22_34") (pintype "bidirectional"))
    )
    (net (code "149") (name "unconnected-(J2-GPIO23-Pad35)") (class "Default")
      (node (ref "J2") (pin "35") (pinfunction "GPIO23_35") (pintype "bidirectional"))
    )
    (net (code "150") (name "unconnected-(J2-GPIO24-Pad36)") (class "Default")
      (node (ref "J2") (pin "36") (pinfunction "GPIO24_36") (pintype "bidirectional"))
    )
    (net (code "151") (name "unconnected-(J2-GPIO25-Pad37)") (class "Default")
      (node (ref "J2") (pin "37") (pinfunction "GPIO25_37") (pintype "bidirectional"))
    )
    (net (code "152") (name "unconnected-(J2-GPIO26_{slash}_ADC0-Pad38)") (class "Default")
      (node (ref "J2") (pin "38") (pinfunction "GPIO26_/_ADC0_38") (pintype "bidirectional"))
    )
    (net (code "153") (name "unconnected-(J2-GPIO27_{slash}_ADC1-Pad39)") (class "Default")
      (node (ref "J2") (pin "39") (pinfunction "GPIO27_/_ADC1_39") (pintype "bidirectional"))
    )
    (net (code "154") (name "unconnected-(J2-GPIO28_{slash}_ADC2-Pad40)") (class "Default")
      (node (ref "J2") (pin "40") (pinfunction "GPIO28_/_ADC2_40") (pintype "bidirectional"))
    )
    (net (code "155") (name "unconnected-(J2-GPIO29_{slash}_ADC3-Pad41)") (class "Default")
      (node (ref "J2") (pin "41") (pinfunction "GPIO29_/_ADC3_41") (pintype "bidirectional"))
    )
    (net (code "156") (name "unconnected-(J2-RUN-Pad26)") (class "Default")
      (node (ref "J2") (pin "26") (pinfunction "RUN_26") (pintype "bidirectional"))
    )
    (net (code "157") (name "unconnected-(L5-Pad2)") (class "Default")
      (node (ref "L5") (pin "2") (pinfunction "2_2") (pintype "passive"))
    )
    (net (code "158") (name "unconnected-(LS1-+-Pad1)") (class "Default")
      (node (ref "LS1") (pin "1") (pinfunction "+_1") (pintype "bidirectional"))
    )
    (net (code "159") (name "unconnected-(S2-Pad1)") (class "Default")
      (node (ref "S2") (pin "1") (pinfunction "1_1") (pintype "passive"))
    )
    (net (code "160") (name "unconnected-(S2-Pad3)") (class "Default")
      (node (ref "S2") (pin "3") (pinfunction "3_3") (pintype "passive"))
    )
    (net (code "161") (name "unconnected-(U9-VCC-Pad1)") (class "Default")
      (node (ref "U9") (pin "1") (pinfunction "VCC_1") (pintype "power_in"))
    )
    (net (code "162") (name "unconnected-(U10-NC_1-Pad3)") (class "Default")
      (node (ref "U10") (pin "3") (pinfunction "NC_1_3") (pintype "bidirectional"))
    )
    (net (code "163") (name "unconnected-(U10-NC_2-Pad4)") (class "Default")
      (node (ref "U10") (pin "4") (pinfunction "NC_2_4") (pintype "bidirectional"))
    )
    (net (code "164") (name "unconnected-(U10-NC_3-Pad9)") (class "Default")
      (node (ref "U10") (pin "9") (pinfunction "NC_3_9") (pintype "bidirectional"))
    )
    (net (code "165") (name "unconnected-(U10-NC_4-Pad10)") (class "Default")
      (node (ref "U10") (pin "10") (pinfunction "NC_4_10") (pintype "bidirectional"))
    )
    (net (code "166") (name "unconnected-(U10-NC_5-Pad14)") (class "Default")
      (node (ref "U10") (pin "14") (pinfunction "NC_5_14") (pintype "bidirectional"))
    )
    (net (code "167") (name "unconnected-(U10-NC_6-Pad15)") (class "Default")
      (node (ref "U10") (pin "15") (pinfunction "NC_6_15") (pintype "bidirectional"))
    )
    (net (code "168") (name "unconnected-(U10-TST1-Pad6)") (class "Default")
      (node (ref "U10") (pin "6") (pinfunction "TST1_6") (pintype "bidirectional"))
    )
    (net (code "169") (name "unconnected-(U10-TST2-Pad7)") (class "Default")
      (node (ref "U10") (pin "7") (pinfunction "TST2_7") (pintype "bidirectional"))
    )
    (net (code "170") (name "unconnected-(U10-TST3-Pad8)") (class "Default")
      (node (ref "U10") (pin "8") (pinfunction "TST3_8") (pintype "bidirectional"))
    )
    (net (code "171") (name "unconnected-(U10-VBUS-Pad16)") (class "Default")
      (node (ref "U10") (pin "16") (pinfunction "VBUS_16") (pintype "bidirectional"))
    )
    (net (code "172") (name "unconnected-(U10-VBUSG-Pad1)") (class "Default")
      (node (ref "U10") (pin "1") (pinfunction "VBUSG_1") (pintype "bidirectional"))
    )
  )
)
